# 85-2031.net
KiCad netlist of a schematic drawn in EAGLE
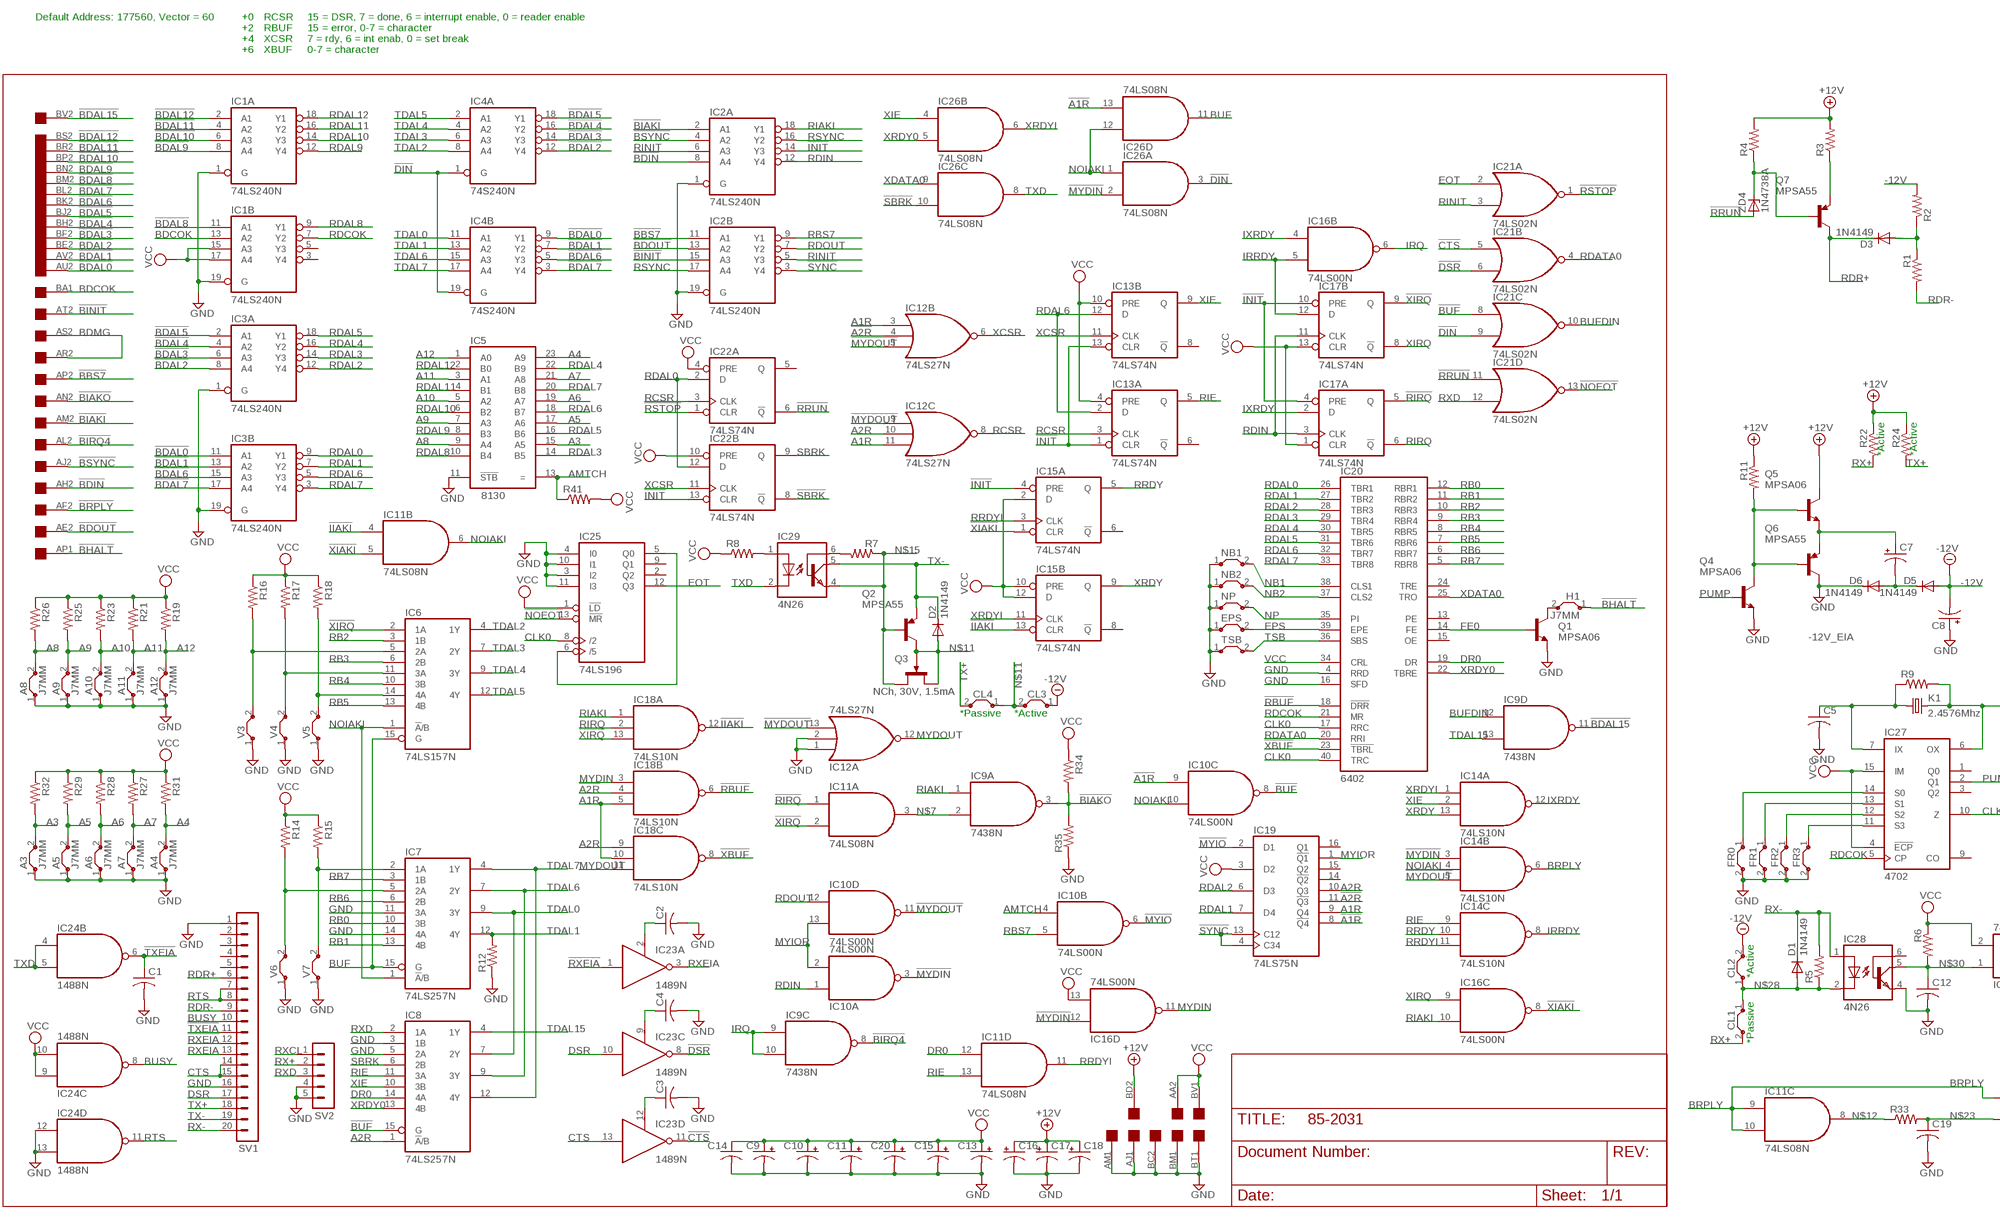
[diagram p0: schematic, sheet 1, part 1 of 2]
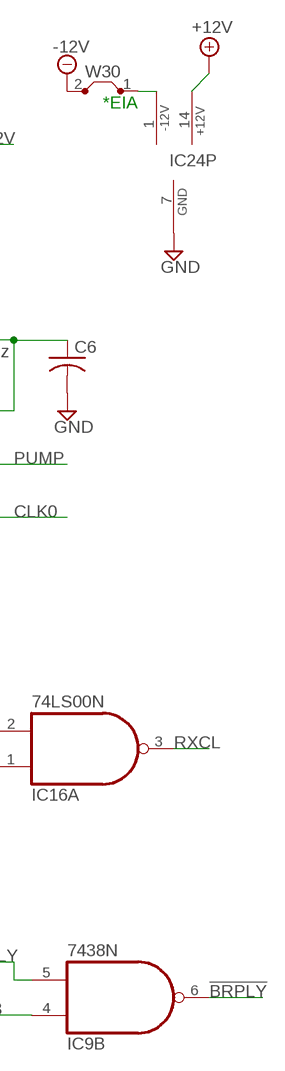
[diagram p1: schematic, sheet 1, part 2 of 2]

(export (version "E")
  (design (tool "Eeschema 10.0.6"))
  (components
    (comp (ref "A3")
      (value "J7MM")
      (footprint "eagle-import:07")
      (libsource (lib "eagle-import") (part "J7MM"))
    )
    (comp (ref "A4")
      (value "J7MM")
      (footprint "eagle-import:07")
      (libsource (lib "eagle-import") (part "J7MM"))
    )
    (comp (ref "A5")
      (value "J7MM")
      (footprint "eagle-import:07")
      (libsource (lib "eagle-import") (part "J7MM"))
    )
    (comp (ref "A6")
      (value "J7MM")
      (footprint "eagle-import:07")
      (libsource (lib "eagle-import") (part "J7MM"))
    )
    (comp (ref "A7")
      (value "J7MM")
      (footprint "eagle-import:07")
      (libsource (lib "eagle-import") (part "J7MM"))
    )
    (comp (ref "A8")
      (value "J7MM")
      (footprint "eagle-import:07")
      (libsource (lib "eagle-import") (part "J7MM"))
    )
    (comp (ref "A9")
      (value "J7MM")
      (footprint "eagle-import:07")
      (libsource (lib "eagle-import") (part "J7MM"))
    )
    (comp (ref "A10")
      (value "J7MM")
      (footprint "eagle-import:07")
      (libsource (lib "eagle-import") (part "J7MM"))
    )
    (comp (ref "A11")
      (value "J7MM")
      (footprint "eagle-import:07")
      (libsource (lib "eagle-import") (part "J7MM"))
    )
    (comp (ref "A12")
      (value "J7MM")
      (footprint "eagle-import:07")
      (libsource (lib "eagle-import") (part "J7MM"))
    )
    (comp (ref "C1")
      (value "C-US075-032X103")
      (footprint "eagle-import:C075-032X103")
      (libsource (lib "eagle-import") (part "C-US075-032X103"))
    )
    (comp (ref "C2")
      (value "C-US075-032X103")
      (footprint "eagle-import:C075-032X103")
      (libsource (lib "eagle-import") (part "C-US075-032X103"))
    )
    (comp (ref "C3")
      (value "C-US075-032X103")
      (footprint "eagle-import:C075-032X103")
      (libsource (lib "eagle-import") (part "C-US075-032X103"))
    )
    (comp (ref "C4")
      (value "C-US075-032X103")
      (footprint "eagle-import:C075-032X103")
      (libsource (lib "eagle-import") (part "C-US075-032X103"))
    )
    (comp (ref "C5")
      (value "C-US075-032X103")
      (footprint "eagle-import:C075-032X103")
      (libsource (lib "eagle-import") (part "C-US075-032X103"))
    )
    (comp (ref "C6")
      (value "C-US075-032X103")
      (footprint "eagle-import:C075-032X103")
      (libsource (lib "eagle-import") (part "C-US075-032X103"))
    )
    (comp (ref "C7")
      (value "CPOL-USB45181B")
      (footprint "eagle-import:B45181B")
      (libsource (lib "eagle-import") (part "CPOL-USB45181B"))
    )
    (comp (ref "C8")
      (value "CPOL-USB45181B")
      (footprint "eagle-import:B45181B")
      (libsource (lib "eagle-import") (part "CPOL-USB45181B"))
    )
    (comp (ref "C9")
      (value "CPOL-USB45181B")
      (footprint "eagle-import:B45181B")
      (libsource (lib "eagle-import") (part "CPOL-USB45181B"))
    )
    (comp (ref "C10")
      (value "CPOL-USB45181B")
      (footprint "eagle-import:B45181B")
      (libsource (lib "eagle-import") (part "CPOL-USB45181B"))
    )
    (comp (ref "C11")
      (value "CPOL-USB45181B")
      (footprint "eagle-import:B45181B")
      (libsource (lib "eagle-import") (part "CPOL-USB45181B"))
    )
    (comp (ref "C12")
      (value "C-US075-032X103")
      (footprint "eagle-import:C075-032X103")
      (libsource (lib "eagle-import") (part "C-US075-032X103"))
    )
    (comp (ref "C13")
      (value "CPOL-USB45181B")
      (footprint "eagle-import:B45181B")
      (libsource (lib "eagle-import") (part "CPOL-USB45181B"))
    )
    (comp (ref "C14")
      (value "C-US075-032X103")
      (footprint "eagle-import:C075-032X103")
      (libsource (lib "eagle-import") (part "C-US075-032X103"))
    )
    (comp (ref "C15")
      (value "CPOL-USB45181B")
      (footprint "eagle-import:B45181B")
      (libsource (lib "eagle-import") (part "CPOL-USB45181B"))
    )
    (comp (ref "C16")
      (value "CPOL-USB45181B")
      (footprint "eagle-import:B45181B")
      (libsource (lib "eagle-import") (part "CPOL-USB45181B"))
    )
    (comp (ref "C17")
      (value "CPOL-USB45181B")
      (footprint "eagle-import:B45181B")
      (libsource (lib "eagle-import") (part "CPOL-USB45181B"))
    )
    (comp (ref "C18")
      (value "CPOL-USB45181B")
      (footprint "eagle-import:B45181B")
      (libsource (lib "eagle-import") (part "CPOL-USB45181B"))
    )
    (comp (ref "C19")
      (value "C-US075-032X103")
      (footprint "eagle-import:C075-032X103")
      (libsource (lib "eagle-import") (part "C-US075-032X103"))
    )
    (comp (ref "C20")
      (value "CPOL-USB45181B")
      (footprint "eagle-import:B45181B")
      (libsource (lib "eagle-import") (part "CPOL-USB45181B"))
    )
    (comp (ref "CL1")
      (value "J7MM")
      (footprint "eagle-import:07")
      (libsource (lib "eagle-import") (part "J7MM"))
    )
    (comp (ref "CL2")
      (value "J7MM")
      (footprint "eagle-import:07")
      (libsource (lib "eagle-import") (part "J7MM"))
    )
    (comp (ref "CL3")
      (value "J7MM")
      (footprint "eagle-import:07")
      (libsource (lib "eagle-import") (part "J7MM"))
    )
    (comp (ref "CL4")
      (value "J7MM")
      (footprint "eagle-import:07")
      (libsource (lib "eagle-import") (part "J7MM"))
    )
    (comp (ref "D1")
      (value "1N4149")
      (footprint "eagle-import:DO35-10")
      (libsource (lib "eagle-import") (part "1N4148DO35-10"))
    )
    (comp (ref "D2")
      (value "1N4149")
      (footprint "eagle-import:DO35-10")
      (libsource (lib "eagle-import") (part "1N4148DO35-10"))
    )
    (comp (ref "D3")
      (value "1N4149")
      (footprint "eagle-import:DO35-10")
      (libsource (lib "eagle-import") (part "1N4148DO35-10"))
    )
    (comp (ref "D5")
      (value "1N4149")
      (footprint "eagle-import:DO35-10")
      (libsource (lib "eagle-import") (part "1N4148DO35-10"))
    )
    (comp (ref "D6")
      (value "1N4149")
      (footprint "eagle-import:DO35-10")
      (libsource (lib "eagle-import") (part "1N4148DO35-10"))
    )
    (comp (ref "EDGE$")
      (value "DOUBLE")
      (footprint "eagle-import:EDGE-CON4")
      (libsource (lib "eagle-import") (part "DOUBLE"))
    )
    (comp (ref "EPS")
      (value "J7MM")
      (footprint "eagle-import:07")
      (libsource (lib "eagle-import") (part "J7MM"))
    )
    (comp (ref "FR0")
      (value "J7MM")
      (footprint "eagle-import:07")
      (libsource (lib "eagle-import") (part "J7MM"))
    )
    (comp (ref "FR1")
      (value "J7MM")
      (footprint "eagle-import:07")
      (libsource (lib "eagle-import") (part "J7MM"))
    )
    (comp (ref "FR2")
      (value "J7MM")
      (footprint "eagle-import:07")
      (libsource (lib "eagle-import") (part "J7MM"))
    )
    (comp (ref "FR3")
      (value "J7MM")
      (footprint "eagle-import:07")
      (libsource (lib "eagle-import") (part "J7MM"))
    )
    (comp (ref "H1")
      (value "J7MM")
      (footprint "eagle-import:07")
      (libsource (lib "eagle-import") (part "J7MM"))
    )
    (comp (ref "IC1")
      (value "74LS240N")
      (footprint "eagle-import:DIL20")
      (libsource (lib "eagle-import") (part "74240NLS"))
    )
    (comp (ref "IC2")
      (value "74LS240N")
      (footprint "eagle-import:DIL20")
      (libsource (lib "eagle-import") (part "74240NLS"))
    )
    (comp (ref "IC3")
      (value "74LS240N")
      (footprint "eagle-import:DIL20")
      (libsource (lib "eagle-import") (part "74240NLS"))
    )
    (comp (ref "IC4")
      (value "74S240N")
      (footprint "eagle-import:DIL20")
      (libsource (lib "eagle-import") (part "74240NS"))
    )
    (comp (ref "IC5")
      (value "8130")
      (footprint "eagle-import:DIL24")
      (libsource (lib "eagle-import") (part "8130"))
    )
    (comp (ref "IC6")
      (value "74LS157N")
      (footprint "eagle-import:DIL16")
      (libsource (lib "eagle-import") (part "74157NLS"))
    )
    (comp (ref "IC7")
      (value "74LS257N")
      (footprint "eagle-import:DIL16")
      (libsource (lib "eagle-import") (part "74257NLS"))
    )
    (comp (ref "IC8")
      (value "74LS257N")
      (footprint "eagle-import:DIL16")
      (libsource (lib "eagle-import") (part "74257NLS"))
    )
    (comp (ref "IC9")
      (value "7438N")
      (footprint "eagle-import:DIL14")
      (libsource (lib "eagle-import") (part "7438NLS"))
    )
    (comp (ref "IC10")
      (value "74LS00N")
      (footprint "eagle-import:DIL14")
      (libsource (lib "eagle-import") (part "7400NLS"))
    )
    (comp (ref "IC11")
      (value "74LS08N")
      (footprint "eagle-import:DIL14")
      (libsource (lib "eagle-import") (part "7408NLS"))
    )
    (comp (ref "IC12")
      (value "74LS27N")
      (footprint "eagle-import:DIL14")
      (libsource (lib "eagle-import") (part "7427NLS"))
    )
    (comp (ref "IC13")
      (value "74LS74N")
      (footprint "eagle-import:DIL14")
      (libsource (lib "eagle-import") (part "7474NLS"))
    )
    (comp (ref "IC14")
      (value "74LS10N")
      (footprint "eagle-import:DIL14")
      (libsource (lib "eagle-import") (part "7410NLS"))
    )
    (comp (ref "IC15")
      (value "74LS74N")
      (footprint "eagle-import:DIL14")
      (libsource (lib "eagle-import") (part "7474NLS"))
    )
    (comp (ref "IC16")
      (value "74LS00N")
      (footprint "eagle-import:DIL14")
      (libsource (lib "eagle-import") (part "7400NLS"))
    )
    (comp (ref "IC17")
      (value "74LS74N")
      (footprint "eagle-import:DIL14")
      (libsource (lib "eagle-import") (part "7474NLS"))
    )
    (comp (ref "IC18")
      (value "74LS10N")
      (footprint "eagle-import:DIL14")
      (libsource (lib "eagle-import") (part "7410NLS"))
    )
    (comp (ref "IC19")
      (value "74LS75N")
      (footprint "eagle-import:DIL16")
      (libsource (lib "eagle-import") (part "7475NLS"))
    )
    (comp (ref "IC20")
      (value "6402")
      (footprint "eagle-import:DIL40")
      (libsource (lib "eagle-import") (part "HD6402"))
    )
    (comp (ref "IC21")
      (value "74LS02N")
      (footprint "eagle-import:DIL14")
      (libsource (lib "eagle-import") (part "7402NLS"))
    )
    (comp (ref "IC22")
      (value "74LS74N")
      (footprint "eagle-import:DIL14")
      (libsource (lib "eagle-import") (part "7474NLS"))
    )
    (comp (ref "IC23")
      (value "1489N")
      (footprint "eagle-import:DIL14")
      (libsource (lib "eagle-import") (part "1489N"))
    )
    (comp (ref "IC24")
      (value "1488N")
      (footprint "eagle-import:DIL14")
      (libsource (lib "eagle-import") (part "1488N"))
    )
    (comp (ref "IC25")
      (value "74LS196")
      (footprint "eagle-import:DIL14")
      (libsource (lib "eagle-import") (part "74LS196"))
    )
    (comp (ref "IC26")
      (value "74LS08N")
      (footprint "eagle-import:DIL14")
      (libsource (lib "eagle-import") (part "7408NLS"))
    )
    (comp (ref "IC27")
      (value "4702")
      (footprint "eagle-import:DIL16")
      (libsource (lib "eagle-import") (part "HD4702"))
    )
    (comp (ref "IC28")
      (value "4N26")
      (footprint "eagle-import:DIL06")
      (fields (field (name "MF") "FAIRCHILD SEMICONDUCTOR") (field (name "MPN") "4N35"))
      (libsource (lib "eagle-import") (part "4N35"))
    )
    (comp (ref "IC29")
      (value "4N26")
      (footprint "eagle-import:DIL06")
      (fields (field (name "MF") "FAIRCHILD SEMICONDUCTOR") (field (name "MPN") "4N35"))
      (libsource (lib "eagle-import") (part "4N35"))
    )
    (comp (ref "K1")
      (value "2.4576Mhz")
      (footprint "eagle-import:HC33U-H")
      (libsource (lib "eagle-import") (part "CRYSTALHC33U-H"))
    )
    (comp (ref "NB1")
      (value "J7MM")
      (footprint "eagle-import:07")
      (libsource (lib "eagle-import") (part "J7MM"))
    )
    (comp (ref "NB2")
      (value "J7MM")
      (footprint "eagle-import:07")
      (libsource (lib "eagle-import") (part "J7MM"))
    )
    (comp (ref "NP")
      (value "J7MM")
      (footprint "eagle-import:07")
      (libsource (lib "eagle-import") (part "J7MM"))
    )
    (comp (ref "Q1")
      (value "MPSA06")
      (footprint "eagle-import:TO92L")
      (libsource (lib "eagle-import") (part "-NPN-TO92L"))
    )
    (comp (ref "Q2")
      (value "MPSA55")
      (footprint "eagle-import:TO92L")
      (libsource (lib "eagle-import") (part "-PNP-TO92L"))
    )
    (comp (ref "Q3")
      (value "NCh, 30V, 1.5mA")
      (footprint "eagle-import:TO18E")
      (libsource (lib "eagle-import") (part "2N4391"))
    )
    (comp (ref "Q4")
      (value "MPSA06")
      (footprint "eagle-import:TO92L")
      (libsource (lib "eagle-import") (part "-NPN-TO92L"))
    )
    (comp (ref "Q5")
      (value "MPSA06")
      (footprint "eagle-import:TO92L")
      (libsource (lib "eagle-import") (part "-NPN-TO92L"))
    )
    (comp (ref "Q6")
      (value "MPSA55")
      (footprint "eagle-import:TO92L")
      (libsource (lib "eagle-import") (part "-PNP-TO92L"))
    )
    (comp (ref "Q7")
      (value "MPSA55")
      (footprint "eagle-import:TO92L")
      (libsource (lib "eagle-import") (part "-PNP-TO92L"))
    )
    (comp (ref "R1")
      (value "R-US_0207/10")
      (footprint "eagle-import:0207_10")
      (libsource (lib "eagle-import") (part "R-US_0207/10"))
    )
    (comp (ref "R2")
      (value "R-US_0207/10")
      (footprint "eagle-import:0207_10")
      (libsource (lib "eagle-import") (part "R-US_0207/10"))
    )
    (comp (ref "R3")
      (value "R-US_0207/10")
      (footprint "eagle-import:0207_10")
      (libsource (lib "eagle-import") (part "R-US_0207/10"))
    )
    (comp (ref "R4")
      (value "R-US_0207/10")
      (footprint "eagle-import:0207_10")
      (libsource (lib "eagle-import") (part "R-US_0207/10"))
    )
    (comp (ref "R5")
      (value "R-US_0207/10")
      (footprint "eagle-import:0207_10")
      (libsource (lib "eagle-import") (part "R-US_0207/10"))
    )
    (comp (ref "R6")
      (value "R-US_0207/10")
      (footprint "eagle-import:0207_10")
      (libsource (lib "eagle-import") (part "R-US_0207/10"))
    )
    (comp (ref "R7")
      (value "R-US_0207/10")
      (footprint "eagle-import:0207_10")
      (libsource (lib "eagle-import") (part "R-US_0207/10"))
    )
    (comp (ref "R8")
      (value "R-US_0207/10")
      (footprint "eagle-import:0207_10")
      (libsource (lib "eagle-import") (part "R-US_0207/10"))
    )
    (comp (ref "R9")
      (value "R-US_0207/10")
      (footprint "eagle-import:0207_10")
      (libsource (lib "eagle-import") (part "R-US_0207/10"))
    )
    (comp (ref "R11")
      (value "R-US_0411/12")
      (footprint "eagle-import:0411_12")
      (libsource (lib "eagle-import") (part "R-US_0411/12"))
    )
    (comp (ref "R12")
      (value "R-US_0207/10")
      (footprint "eagle-import:0207_10")
      (libsource (lib "eagle-import") (part "R-US_0207/10"))
    )
    (comp (ref "R14")
      (value "R-US_0207/10")
      (footprint "eagle-import:0207_10")
      (libsource (lib "eagle-import") (part "R-US_0207/10"))
    )
    (comp (ref "R15")
      (value "R-US_0207/10")
      (footprint "eagle-import:0207_10")
      (libsource (lib "eagle-import") (part "R-US_0207/10"))
    )
    (comp (ref "R16")
      (value "R-US_0207/10")
      (footprint "eagle-import:0207_10")
      (libsource (lib "eagle-import") (part "R-US_0207/10"))
    )
    (comp (ref "R17")
      (value "R-US_0207/10")
      (footprint "eagle-import:0207_10")
      (libsource (lib "eagle-import") (part "R-US_0207/10"))
    )
    (comp (ref "R18")
      (value "R-US_0207/10")
      (footprint "eagle-import:0207_10")
      (libsource (lib "eagle-import") (part "R-US_0207/10"))
    )
    (comp (ref "R19")
      (value "R-US_0207/10")
      (footprint "eagle-import:0207_10")
      (libsource (lib "eagle-import") (part "R-US_0207/10"))
    )
    (comp (ref "R21")
      (value "R-US_0207/10")
      (footprint "eagle-import:0207_10")
      (libsource (lib "eagle-import") (part "R-US_0207/10"))
    )
    (comp (ref "R22")
      (value "R-US_0207/10")
      (footprint "eagle-import:0207_10")
      (libsource (lib "eagle-import") (part "R-US_0207/10"))
    )
    (comp (ref "R23")
      (value "R-US_0207/10")
      (footprint "eagle-import:0207_10")
      (libsource (lib "eagle-import") (part "R-US_0207/10"))
    )
    (comp (ref "R24")
      (value "R-US_0207/10")
      (footprint "eagle-import:0207_10")
      (libsource (lib "eagle-import") (part "R-US_0207/10"))
    )
    (comp (ref "R25")
      (value "R-US_0207/10")
      (footprint "eagle-import:0207_10")
      (libsource (lib "eagle-import") (part "R-US_0207/10"))
    )
    (comp (ref "R26")
      (value "R-US_0207/10")
      (footprint "eagle-import:0207_10")
      (libsource (lib "eagle-import") (part "R-US_0207/10"))
    )
    (comp (ref "R27")
      (value "R-US_0207/10")
      (footprint "eagle-import:0207_10")
      (libsource (lib "eagle-import") (part "R-US_0207/10"))
    )
    (comp (ref "R28")
      (value "R-US_0207/10")
      (footprint "eagle-import:0207_10")
      (libsource (lib "eagle-import") (part "R-US_0207/10"))
    )
    (comp (ref "R29")
      (value "R-US_0207/10")
      (footprint "eagle-import:0207_10")
      (libsource (lib "eagle-import") (part "R-US_0207/10"))
    )
    (comp (ref "R31")
      (value "R-US_0207/10")
      (footprint "eagle-import:0207_10")
      (libsource (lib "eagle-import") (part "R-US_0207/10"))
    )
    (comp (ref "R32")
      (value "R-US_0207/10")
      (footprint "eagle-import:0207_10")
      (libsource (lib "eagle-import") (part "R-US_0207/10"))
    )
    (comp (ref "R33")
      (value "R-US_0207/10")
      (footprint "eagle-import:0207_10")
      (libsource (lib "eagle-import") (part "R-US_0207/10"))
    )
    (comp (ref "R34")
      (value "R-US_0207/10")
      (footprint "eagle-import:0207_10")
      (libsource (lib "eagle-import") (part "R-US_0207/10"))
    )
    (comp (ref "R35")
      (value "R-US_0207/10")
      (footprint "eagle-import:0207_10")
      (libsource (lib "eagle-import") (part "R-US_0207/10"))
    )
    (comp (ref "R41")
      (value "R-US_0207/10")
      (footprint "eagle-import:0207_10")
      (libsource (lib "eagle-import") (part "R-US_0207/10"))
    )
    (comp (ref "SV1")
      (value "MA20-1")
      (footprint "eagle-import:MA20-1")
      (libsource (lib "eagle-import") (part "MA20-1"))
    )
    (comp (ref "SV2")
      (value "MA05-1")
      (footprint "eagle-import:MA05-1")
      (libsource (lib "eagle-import") (part "MA05-1"))
    )
    (comp (ref "TSB")
      (value "J7MM")
      (footprint "eagle-import:07")
      (libsource (lib "eagle-import") (part "J7MM"))
    )
    (comp (ref "V3")
      (value "J7MM")
      (footprint "eagle-import:07")
      (libsource (lib "eagle-import") (part "J7MM"))
    )
    (comp (ref "V4")
      (value "J7MM")
      (footprint "eagle-import:07")
      (libsource (lib "eagle-import") (part "J7MM"))
    )
    (comp (ref "V5")
      (value "J7MM")
      (footprint "eagle-import:07")
      (libsource (lib "eagle-import") (part "J7MM"))
    )
    (comp (ref "V6")
      (value "J7MM")
      (footprint "eagle-import:07")
      (libsource (lib "eagle-import") (part "J7MM"))
    )
    (comp (ref "V7")
      (value "J7MM")
      (footprint "eagle-import:07")
      (libsource (lib "eagle-import") (part "J7MM"))
    )
    (comp (ref "W30")
      (value "J7MM")
      (footprint "eagle-import:07")
      (libsource (lib "eagle-import") (part "J7MM"))
    )
    (comp (ref "ZD4")
      (value "1N4738A")
      (footprint "eagle-import:DO41Z10")
      (libsource (lib "eagle-import") (part "1N4728"))
    )
  )
  (nets
    (net (code "1") (name "+12V") (class "Default")
      (node (ref "C16") (pin "+") (pinfunction "+_+") (pintype "passive"))
      (node (ref "C17") (pin "+") (pinfunction "+_+") (pintype "passive"))
      (node (ref "C18") (pin "+") (pinfunction "+_+") (pintype "passive"))
      (node (ref "EDGE$") (pin "BD2") (pinfunction "1_BD2") (pintype "bidirectional"))
      (node (ref "IC24") (pin "14") (pinfunction "+12V_14") (pintype "power_in"))
      (node (ref "Q5") (pin "3") (pinfunction "C_3") (pintype "passive"))
      (node (ref "R11") (pin "1") (pinfunction "1_1") (pintype "passive"))
      (node (ref "R22") (pin "1") (pinfunction "1_1") (pintype "passive"))
      (node (ref "R24") (pin "1") (pinfunction "1_1") (pintype "passive"))
      (node (ref "R3") (pin "2") (pinfunction "2_2") (pintype "passive"))
      (node (ref "R4") (pin "2") (pinfunction "2_2") (pintype "passive"))
    )
    (net (code "2") (name "-12V") (class "Default")
      (node (ref "C8") (pin "-") (pinfunction "-_-") (pintype "passive"))
      (node (ref "CL2") (pin "2") (pinfunction "2_2") (pintype "passive"))
      (node (ref "CL3") (pin "1") (pinfunction "1_1") (pintype "passive"))
      (node (ref "D5") (pin "A") (pinfunction "A_A") (pintype "passive"))
      (node (ref "R2") (pin "2") (pinfunction "2_2") (pintype "passive"))
      (node (ref "W30") (pin "2") (pinfunction "2_2") (pintype "passive"))
    )
    (net (code "3") (name "/-12V_EIA") (class "Default")
      (node (ref "IC24") (pin "1") (pinfunction "-12V_1") (pintype "power_in"))
      (node (ref "W30") (pin "1") (pinfunction "1_1") (pintype "passive"))
    )
    (net (code "4") (name "/A1R") (class "Default")
      (node (ref "IC12") (pin "11") (pinfunction "I2_11") (pintype "input"))
      (node (ref "IC12") (pin "3") (pinfunction "I0_3") (pintype "input"))
      (node (ref "IC18") (pin "10") (pinfunction "I1_10") (pintype "input"))
      (node (ref "IC18") (pin "5") (pinfunction "I2_5") (pintype "input"))
      (node (ref "IC19") (pin "9") (pinfunction "Q4_9") (pintype "output"))
    )
    (net (code "5") (name "/A2R") (class "Default")
      (node (ref "IC12") (pin "10") (pinfunction "I1_10") (pintype "input"))
      (node (ref "IC18") (pin "9") (pinfunction "I0_9") (pintype "input"))
      (node (ref "IC19") (pin "10") (pinfunction "Q3_10") (pintype "output"))
      (node (ref "IC8") (pin "1") (pinfunction "~{A}/B_1") (pintype "input"))
    )
    (net (code "6") (name "/A3") (class "Default")
      (node (ref "A3") (pin "2") (pinfunction "2_2") (pintype "passive"))
      (node (ref "IC5") (pin "15") (pinfunction "A5_15") (pintype "input"))
      (node (ref "R32") (pin "2") (pinfunction "2_2") (pintype "passive"))
    )
    (net (code "7") (name "/A4") (class "Default")
      (node (ref "A4") (pin "2") (pinfunction "2_2") (pintype "passive"))
      (node (ref "IC5") (pin "23") (pinfunction "A9_23") (pintype "input"))
      (node (ref "R31") (pin "2") (pinfunction "2_2") (pintype "passive"))
    )
    (net (code "8") (name "/A5") (class "Default")
      (node (ref "A5") (pin "2") (pinfunction "2_2") (pintype "passive"))
      (node (ref "IC5") (pin "17") (pinfunction "A6_17") (pintype "input"))
      (node (ref "R29") (pin "2") (pinfunction "2_2") (pintype "passive"))
    )
    (net (code "9") (name "/A6") (class "Default")
      (node (ref "A6") (pin "2") (pinfunction "2_2") (pintype "passive"))
      (node (ref "IC5") (pin "19") (pinfunction "A7_19") (pintype "input"))
      (node (ref "R28") (pin "2") (pinfunction "2_2") (pintype "passive"))
    )
    (net (code "10") (name "/A7") (class "Default")
      (node (ref "A7") (pin "2") (pinfunction "2_2") (pintype "passive"))
      (node (ref "IC5") (pin "21") (pinfunction "A8_21") (pintype "input"))
      (node (ref "R27") (pin "2") (pinfunction "2_2") (pintype "passive"))
    )
    (net (code "11") (name "/A8") (class "Default")
      (node (ref "A8") (pin "2") (pinfunction "2_2") (pintype "passive"))
      (node (ref "IC5") (pin "9") (pinfunction "A4_9") (pintype "input"))
      (node (ref "R26") (pin "2") (pinfunction "2_2") (pintype "passive"))
    )
    (net (code "12") (name "/A9") (class "Default")
      (node (ref "A9") (pin "2") (pinfunction "2_2") (pintype "passive"))
      (node (ref "IC5") (pin "7") (pinfunction "A3_7") (pintype "input"))
      (node (ref "R25") (pin "2") (pinfunction "2_2") (pintype "passive"))
    )
    (net (code "13") (name "/A10") (class "Default")
      (node (ref "A10") (pin "2") (pinfunction "2_2") (pintype "passive"))
      (node (ref "IC5") (pin "5") (pinfunction "A2_5") (pintype "input"))
      (node (ref "R23") (pin "2") (pinfunction "2_2") (pintype "passive"))
    )
    (net (code "14") (name "/A11") (class "Default")
      (node (ref "A11") (pin "2") (pinfunction "2_2") (pintype "passive"))
      (node (ref "IC5") (pin "3") (pinfunction "A1_3") (pintype "input"))
      (node (ref "R21") (pin "2") (pinfunction "2_2") (pintype "passive"))
    )
    (net (code "15") (name "/A12") (class "Default")
      (node (ref "A12") (pin "2") (pinfunction "2_2") (pintype "passive"))
      (node (ref "IC5") (pin "1") (pinfunction "A0_1") (pintype "input"))
      (node (ref "R19") (pin "2") (pinfunction "2_2") (pintype "passive"))
    )
    (net (code "16") (name "/AMTCH") (class "Default")
      (node (ref "IC10") (pin "4") (pinfunction "I0_4") (pintype "input"))
      (node (ref "IC5") (pin "13") (pinfunction "=_13") (pintype "output"))
      (node (ref "R41") (pin "1") (pinfunction "1_1") (pintype "passive"))
    )
    (net (code "17") (name "/BDCOK") (class "Default")
      (node (ref "EDGE$") (pin "BA1") (pinfunction "1_BA1") (pintype "bidirectional"))
      (node (ref "IC1") (pin "13") (pinfunction "A2_13") (pintype "input"))
    )
    (net (code "18") (name "/BDMG") (class "Default")
      (node (ref "EDGE$") (pin "AR2") (pinfunction "1_AR2") (pintype "bidirectional"))
      (node (ref "EDGE$") (pin "AS2") (pinfunction "1_AS2") (pintype "bidirectional"))
    )
    (net (code "19") (name "/BRPLY") (class "Default")
      (node (ref "IC11") (pin "10") (pinfunction "I1_10") (pintype "input"))
      (node (ref "IC11") (pin "9") (pinfunction "I0_9") (pintype "input"))
      (node (ref "IC14") (pin "6") (pinfunction "O_6") (pintype "output"))
      (node (ref "IC9") (pin "5") (pinfunction "I1_5") (pintype "input"))
    )
    (net (code "20") (name "/BUF") (class "Default")
      (node (ref "IC26") (pin "11") (pinfunction "O_11") (pintype "output"))
      (node (ref "IC6") (pin "15") (pinfunction "G_15") (pintype "input"))
      (node (ref "IC7") (pin "15") (pinfunction "G_15") (pintype "input"))
    )
    (net (code "21") (name "/BUFDIN") (class "Default")
      (node (ref "IC21") (pin "10") (pinfunction "O_10") (pintype "output"))
      (node (ref "IC9") (pin "12") (pinfunction "I0_12") (pintype "input"))
    )
    (net (code "22") (name "/BUSY") (class "Default")
      (node (ref "IC24") (pin "8") (pinfunction "O_8") (pintype "output"))
      (node (ref "SV1") (pin "10") (pinfunction "10_10") (pintype "passive"))
    )
    (net (code "23") (name "/CLK0") (class "Default")
      (node (ref "IC20") (pin "17") (pinfunction "RRC_17") (pintype "input"))
      (node (ref "IC20") (pin "40") (pinfunction "TRC_40") (pintype "input"))
      (node (ref "IC25") (pin "8") (pinfunction "/2_8") (pintype "bidirectional"))
      (node (ref "IC27") (pin "10") (pinfunction "Z_10") (pintype "output"))
    )
    (net (code "24") (name "/CTS") (class "Default")
      (node (ref "IC23") (pin "13") (pinfunction "I_13") (pintype "input"))
      (node (ref "SV1") (pin "14") (pinfunction "14_14") (pintype "passive"))
      (node (ref "SV1") (pin "15") (pinfunction "15_15") (pintype "passive"))
    )
    (net (code "25") (name "/DR0") (class "Default")
      (node (ref "IC11") (pin "12") (pinfunction "I0_12") (pintype "input"))
      (node (ref "IC20") (pin "19") (pinfunction "DR_19") (pintype "tri_state"))
      (node (ref "IC8") (pin "14") (pinfunction "4A_14") (pintype "input"))
    )
    (net (code "26") (name "/DSR") (class "Default")
      (node (ref "IC23") (pin "10") (pinfunction "I_10") (pintype "input"))
      (node (ref "SV1") (pin "17") (pinfunction "17_17") (pintype "passive"))
    )
    (net (code "27") (name "/EOT") (class "Default")
      (node (ref "IC21") (pin "2") (pinfunction "I0_2") (pintype "input"))
      (node (ref "IC25") (pin "12") (pinfunction "Q3_12") (pintype "output"))
    )
    (net (code "28") (name "/EPS") (class "Default")
      (node (ref "EPS") (pin "2") (pinfunction "2_2") (pintype "passive"))
      (node (ref "IC20") (pin "39") (pinfunction "EPE_39") (pintype "input"))
    )
    (net (code "29") (name "/FE0") (class "Default")
      (node (ref "IC20") (pin "14") (pinfunction "FE_14") (pintype "tri_state"))
      (node (ref "Q1") (pin "2") (pinfunction "B_2") (pintype "passive"))
    )
    (net (code "30") (name "/IRQ") (class "Default")
      (node (ref "IC16") (pin "6") (pinfunction "O_6") (pintype "output"))
      (node (ref "IC9") (pin "10") (pinfunction "I1_10") (pintype "input"))
      (node (ref "IC9") (pin "9") (pinfunction "I0_9") (pintype "input"))
    )
    (net (code "31") (name "/IRRDY") (class "Default")
      (node (ref "IC14") (pin "8") (pinfunction "O_8") (pintype "output"))
      (node (ref "IC16") (pin "5") (pinfunction "I1_5") (pintype "input"))
      (node (ref "IC17") (pin "12") (pinfunction "D_12") (pintype "input"))
    )
    (net (code "32") (name "/IXRDY") (class "Default")
      (node (ref "IC14") (pin "12") (pinfunction "O_12") (pintype "output"))
      (node (ref "IC16") (pin "4") (pinfunction "I0_4") (pintype "input"))
      (node (ref "IC17") (pin "2") (pinfunction "D_2") (pintype "input"))
    )
    (net (code "33") (name "/MYDIN") (class "Default")
      (node (ref "IC16") (pin "11") (pinfunction "O_11") (pintype "output"))
      (node (ref "IC18") (pin "3") (pinfunction "I0_3") (pintype "input"))
    )
    (net (code "34") (name "/MYDOUT") (class "Default")
      (node (ref "IC12") (pin "12") (pinfunction "O_12") (pintype "output"))
      (node (ref "IC18") (pin "11") (pinfunction "I2_11") (pintype "input"))
    )
    (net (code "35") (name "/MYIOR") (class "Default")
      (node (ref "IC10") (pin "13") (pinfunction "I1_13") (pintype "input"))
      (node (ref "IC10") (pin "2") (pinfunction "I1_2") (pintype "input"))
      (node (ref "IC19") (pin "1") (pinfunction "~{Q1}_1") (pintype "output"))
    )
    (net (code "36") (name "/N$7") (class "Default")
      (node (ref "IC11") (pin "3") (pinfunction "O_3") (pintype "output"))
      (node (ref "IC9") (pin "2") (pinfunction "I1_2") (pintype "input"))
    )
    (net (code "37") (name "/N$11") (class "Default")
      (node (ref "CL3") (pin "2") (pinfunction "2_2") (pintype "passive"))
      (node (ref "CL4") (pin "1") (pinfunction "1_1") (pintype "passive"))
      (node (ref "D2") (pin "A") (pinfunction "A_A") (pintype "passive"))
      (node (ref "Q2") (pin "3") (pinfunction "C_3") (pintype "passive"))
      (node (ref "Q3") (pin "D") (pinfunction "D_D") (pintype "passive"))
      (node (ref "Q3") (pin "G") (pinfunction "G_G") (pintype "passive"))
    )
    (net (code "38") (name "/N$12") (class "Default")
      (node (ref "IC11") (pin "8") (pinfunction "O_8") (pintype "output"))
      (node (ref "R33") (pin "1") (pinfunction "1_1") (pintype "passive"))
    )
    (net (code "39") (name "/N$15") (class "Default")
      (node (ref "IC29") (pin "4") (pinfunction "EMI_4") (pintype "passive"))
      (node (ref "Q2") (pin "2") (pinfunction "B_2") (pintype "passive"))
      (node (ref "Q3") (pin "S") (pinfunction "S_S") (pintype "passive"))
      (node (ref "R7") (pin "1") (pinfunction "1_1") (pintype "passive"))
    )
    (net (code "40") (name "/N$23") (class "Default")
      (node (ref "C19") (pin "1") (pinfunction "1_1") (pintype "passive"))
      (node (ref "IC9") (pin "4") (pinfunction "I0_4") (pintype "input"))
      (node (ref "R33") (pin "2") (pinfunction "2_2") (pintype "passive"))
    )
    (net (code "41") (name "/N$28") (class "Default")
      (node (ref "CL1") (pin "1") (pinfunction "1_1") (pintype "passive"))
      (node (ref "CL2") (pin "1") (pinfunction "1_1") (pintype "passive"))
      (node (ref "D1") (pin "A") (pinfunction "A_A") (pintype "passive"))
      (node (ref "IC28") (pin "2") (pinfunction "C_2") (pintype "passive"))
      (node (ref "R5") (pin "1") (pinfunction "1_1") (pintype "passive"))
    )
    (net (code "42") (name "/N$30") (class "Default")
      (node (ref "C12") (pin "1") (pinfunction "1_1") (pintype "passive"))
      (node (ref "IC16") (pin "1") (pinfunction "I0_1") (pintype "input"))
      (node (ref "IC28") (pin "5") (pinfunction "COL_5") (pintype "passive"))
      (node (ref "R6") (pin "2") (pinfunction "2_2") (pintype "passive"))
    )
    (net (code "43") (name "/NB1") (class "Default")
      (node (ref "IC20") (pin "38") (pinfunction "CLS1_38") (pintype "input"))
      (node (ref "NB1") (pin "2") (pinfunction "2_2") (pintype "passive"))
    )
    (net (code "44") (name "/NB2") (class "Default")
      (node (ref "IC20") (pin "37") (pinfunction "CLS2_37") (pintype "input"))
      (node (ref "NB2") (pin "2") (pinfunction "2_2") (pintype "passive"))
    )
    (net (code "45") (name "/NOIAKI") (class "Default")
      (node (ref "IC10") (pin "10") (pinfunction "I1_10") (pintype "input"))
      (node (ref "IC11") (pin "6") (pinfunction "O_6") (pintype "output"))
      (node (ref "IC14") (pin "4") (pinfunction "I1_4") (pintype "input"))
      (node (ref "IC26") (pin "1") (pinfunction "I0_1") (pintype "input"))
      (node (ref "IC26") (pin "12") (pinfunction "I0_12") (pintype "input"))
      (node (ref "IC6") (pin "1") (pinfunction "~{A}/B_1") (pintype "input"))
      (node (ref "IC7") (pin "1") (pinfunction "~{A}/B_1") (pintype "input"))
    )
    (net (code "46") (name "/NP") (class "Default")
      (node (ref "IC20") (pin "35") (pinfunction "PI_35") (pintype "input"))
      (node (ref "NP") (pin "2") (pinfunction "2_2") (pintype "passive"))
    )
    (net (code "47") (name "/PUMP") (class "Default")
      (node (ref "IC27") (pin "2") (pinfunction "Q1_2") (pintype "output"))
      (node (ref "Q4") (pin "2") (pinfunction "B_2") (pintype "passive"))
    )
    (net (code "48") (name "/RB0") (class "Default")
      (node (ref "IC20") (pin "12") (pinfunction "RBR1_12") (pintype "tri_state"))
      (node (ref "IC7") (pin "10") (pinfunction "3B_10") (pintype "input"))
    )
    (net (code "49") (name "/RB1") (class "Default")
      (node (ref "IC20") (pin "11") (pinfunction "RBR2_11") (pintype "tri_state"))
      (node (ref "IC7") (pin "13") (pinfunction "4B_13") (pintype "input"))
    )
    (net (code "50") (name "/RB2") (class "Default")
      (node (ref "IC20") (pin "10") (pinfunction "RBR3_10") (pintype "tri_state"))
      (node (ref "IC6") (pin "3") (pinfunction "1B_3") (pintype "input"))
    )
    (net (code "51") (name "/RB3") (class "Default")
      (node (ref "IC20") (pin "9") (pinfunction "RBR4_9") (pintype "tri_state"))
      (node (ref "IC6") (pin "6") (pinfunction "2B_6") (pintype "input"))
    )
    (net (code "52") (name "/RB4") (class "Default")
      (node (ref "IC20") (pin "8") (pinfunction "RBR5_8") (pintype "tri_state"))
      (node (ref "IC6") (pin "10") (pinfunction "3B_10") (pintype "input"))
    )
    (net (code "53") (name "/RB5") (class "Default")
      (node (ref "IC20") (pin "7") (pinfunction "RBR6_7") (pintype "tri_state"))
      (node (ref "IC6") (pin "13") (pinfunction "4B_13") (pintype "input"))
    )
    (net (code "54") (name "/RB6") (class "Default")
      (node (ref "IC20") (pin "6") (pinfunction "RBR7_6") (pintype "tri_state"))
      (node (ref "IC7") (pin "6") (pinfunction "2B_6") (pintype "input"))
    )
    (net (code "55") (name "/RB7") (class "Default")
      (node (ref "IC20") (pin "5") (pinfunction "RBR8_5") (pintype "tri_state"))
      (node (ref "IC7") (pin "3") (pinfunction "1B_3") (pintype "input"))
    )
    (net (code "56") (name "/RBS7") (class "Default")
      (node (ref "IC10") (pin "5") (pinfunction "I1_5") (pintype "input"))
      (node (ref "IC2") (pin "9") (pinfunction "Y1_9") (pintype "tri_state"))
    )
    (net (code "57") (name "/RCSR") (class "Default")
      (node (ref "IC12") (pin "8") (pinfunction "O_8") (pintype "output"))
      (node (ref "IC13") (pin "3") (pinfunction "CLK_3") (pintype "input"))
      (node (ref "IC22") (pin "3") (pinfunction "CLK_3") (pintype "input"))
    )
    (net (code "58") (name "/RDAL0") (class "Default")
      (node (ref "IC20") (pin "26") (pinfunction "TBR1_26") (pintype "input"))
      (node (ref "IC22") (pin "12") (pinfunction "D_12") (pintype "input"))
      (node (ref "IC22") (pin "2") (pinfunction "D_2") (pintype "input"))
      (node (ref "IC3") (pin "9") (pinfunction "Y1_9") (pintype "tri_state"))
    )
    (net (code "59") (name "/RDAL1") (class "Default")
      (node (ref "IC19") (pin "7") (pinfunction "D4_7") (pintype "input"))
      (node (ref "IC20") (pin "27") (pinfunction "TBR2_27") (pintype "input"))
      (node (ref "IC3") (pin "7") (pinfunction "Y2_7") (pintype "tri_state"))
    )
    (net (code "60") (name "/RDAL2") (class "Default")
      (node (ref "IC19") (pin "6") (pinfunction "D3_6") (pintype "input"))
      (node (ref "IC20") (pin "28") (pinfunction "TBR3_28") (pintype "input"))
      (node (ref "IC3") (pin "12") (pinfunction "Y4_12") (pintype "tri_state"))
    )
    (net (code "61") (name "/RDAL3") (class "Default")
      (node (ref "IC20") (pin "29") (pinfunction "TBR4_29") (pintype "input"))
      (node (ref "IC3") (pin "14") (pinfunction "Y3_14") (pintype "tri_state"))
      (node (ref "IC5") (pin "14") (pinfunction "B5_14") (pintype "input"))
    )
    (net (code "62") (name "/RDAL4") (class "Default")
      (node (ref "IC20") (pin "30") (pinfunction "TBR5_30") (pintype "input"))
      (node (ref "IC3") (pin "16") (pinfunction "Y2_16") (pintype "tri_state"))
      (node (ref "IC5") (pin "22") (pinfunction "B9_22") (pintype "input"))
    )
    (net (code "63") (name "/RDAL5") (class "Default")
      (node (ref "IC20") (pin "31") (pinfunction "TBR6_31") (pintype "input"))
      (node (ref "IC3") (pin "18") (pinfunction "Y1_18") (pintype "tri_state"))
      (node (ref "IC5") (pin "16") (pinfunction "B6_16") (pintype "input"))
    )
    (net (code "64") (name "/RDAL6") (class "Default")
      (node (ref "IC13") (pin "12") (pinfunction "D_12") (pintype "input"))
      (node (ref "IC13") (pin "2") (pinfunction "D_2") (pintype "input"))
      (node (ref "IC20") (pin "32") (pinfunction "TBR7_32") (pintype "input"))
      (node (ref "IC3") (pin "5") (pinfunction "Y3_5") (pintype "tri_state"))
      (node (ref "IC5") (pin "18") (pinfunction "B7_18") (pintype "input"))
    )
    (net (code "65") (name "/RDAL7") (class "Default")
      (node (ref "IC20") (pin "33") (pinfunction "TBR8_33") (pintype "input"))
      (node (ref "IC3") (pin "3") (pinfunction "Y4_3") (pintype "tri_state"))
      (node (ref "IC5") (pin "20") (pinfunction "B8_20") (pintype "input"))
    )
    (net (code "66") (name "/RDAL8") (class "Default")
      (node (ref "IC1") (pin "9") (pinfunction "Y1_9") (pintype "tri_state"))
      (node (ref "IC5") (pin "10") (pinfunction "B4_10") (pintype "input"))
    )
    (net (code "67") (name "/RDAL9") (class "Default")
      (node (ref "IC1") (pin "12") (pinfunction "Y4_12") (pintype "tri_state"))
      (node (ref "IC5") (pin "8") (pinfunction "B3_8") (pintype "input"))
    )
    (net (code "68") (name "/RDAL10") (class "Default")
      (node (ref "IC1") (pin "14") (pinfunction "Y3_14") (pintype "tri_state"))
      (node (ref "IC5") (pin "6") (pinfunction "B2_6") (pintype "input"))
    )
    (net (code "69") (name "/RDAL11") (class "Default")
      (node (ref "IC1") (pin "16") (pinfunction "Y2_16") (pintype "tri_state"))
      (node (ref "IC5") (pin "4") (pinfunction "B1_4") (pintype "input"))
    )
    (net (code "70") (name "/RDAL12") (class "Default")
      (node (ref "IC1") (pin "18") (pinfunction "Y1_18") (pintype "tri_state"))
      (node (ref "IC5") (pin "2") (pinfunction "B0_2") (pintype "input"))
    )
    (net (code "71") (name "/RDATA0") (class "Default")
      (node (ref "IC20") (pin "20") (pinfunction "RRI_20") (pintype "input"))
      (node (ref "IC21") (pin "4") (pinfunction "O_4") (pintype "output"))
    )
    (net (code "72") (name "/RDCOK") (class "Default")
      (node (ref "IC1") (pin "7") (pinfunction "Y2_7") (pintype "tri_state"))
      (node (ref "IC20") (pin "21") (pinfunction "MR_21") (pintype "input"))
      (node (ref "IC27") (pin "5") (pinfunction "CP_5") (pintype "input"))
    )
    (net (code "73") (name "/RDIN") (class "Default")
      (node (ref "IC10") (pin "1") (pinfunction "I0_1") (pintype "input"))
      (node (ref "IC17") (pin "11") (pinfunction "CLK_11") (pintype "input"))
      (node (ref "IC17") (pin "3") (pinfunction "CLK_3") (pintype "input"))
      (node (ref "IC2") (pin "12") (pinfunction "Y4_12") (pintype "tri_state"))
    )
    (net (code "74") (name "/RDOUT") (class "Default")
      (node (ref "IC10") (pin "12") (pinfunction "I0_12") (pintype "input"))
      (node (ref "IC2") (pin "7") (pinfunction "Y2_7") (pintype "tri_state"))
    )
    (net (code "75") (name "/RDR+") (class "Default")
      (node (ref "D3") (pin "C") (pinfunction "C_C") (pintype "passive"))
      (node (ref "Q7") (pin "3") (pinfunction "C_3") (pintype "passive"))
      (node (ref "SV1") (pin "6") (pinfunction "6_6") (pintype "passive"))
    )
    (net (code "76") (name "/RDR-") (class "Default")
      (node (ref "R1") (pin "2") (pinfunction "2_2") (pintype "passive"))
      (node (ref "SV1") (pin "9") (pinfunction "9_9") (pintype "passive"))
    )
    (net (code "77") (name "/RIAKI") (class "Default")
      (node (ref "IC16") (pin "10") (pinfunction "I1_10") (pintype "input"))
      (node (ref "IC18") (pin "1") (pinfunction "I0_1") (pintype "input"))
      (node (ref "IC2") (pin "18") (pinfunction "Y1_18") (pintype "tri_state"))
      (node (ref "IC9") (pin "1") (pinfunction "I0_1") (pintype "input"))
    )
    (net (code "78") (name "/RIE") (class "Default")
      (node (ref "IC11") (pin "13") (pinfunction "I1_13") (pintype "input"))
      (node (ref "IC13") (pin "5") (pinfunction "Q_5") (pintype "output"))
      (node (ref "IC14") (pin "9") (pinfunction "I0_9") (pintype "input"))
      (node (ref "IC8") (pin "11") (pinfunction "3A_11") (pintype "input"))
    )
    (net (code "79") (name "/RINIT") (class "Default")
      (node (ref "IC2") (pin "5") (pinfunction "Y3_5") (pintype "tri_state"))
      (node (ref "IC2") (pin "6") (pinfunction "A3_6") (pintype "input"))
      (node (ref "IC21") (pin "3") (pinfunction "I1_3") (pintype "input"))
    )
    (net (code "80") (name "/RIRQ") (class "Default")
      (node (ref "IC17") (pin "6") (pinfunction "~{Q}_6") (pintype "output"))
      (node (ref "IC18") (pin "2") (pinfunction "I1_2") (pintype "input"))
    )
    (net (code "81") (name "/RRDY") (class "Default")
      (node (ref "IC14") (pin "10") (pinfunction "I1_10") (pintype "input"))
      (node (ref "IC15") (pin "5") (pinfunction "Q_5") (pintype "output"))
    )
    (net (code "82") (name "/RRDYI") (class "Default")
      (node (ref "IC11") (pin "11") (pinfunction "O_11") (pintype "output"))
      (node (ref "IC14") (pin "11") (pinfunction "I2_11") (pintype "input"))
      (node (ref "IC15") (pin "3") (pinfunction "CLK_3") (pintype "input"))
    )
    (net (code "83") (name "/RSYNC") (class "Default")
      (node (ref "IC2") (pin "16") (pinfunction "Y2_16") (pintype "tri_state"))
      (node (ref "IC2") (pin "17") (pinfunction "A4_17") (pintype "input"))
    )
    (net (code "84") (name "/RTS") (class "Default")
      (node (ref "IC24") (pin "11") (pinfunction "O_11") (pintype "output"))
      (node (ref "SV1") (pin "7") (pinfunction "7_7") (pintype "passive"))
      (node (ref "SV1") (pin "8") (pinfunction "8_8") (pintype "passive"))
    )
    (net (code "85") (name "/RX+") (class "Default")
      (node (ref "CL1") (pin "2") (pinfunction "2_2") (pintype "passive"))
      (node (ref "R22") (pin "2") (pinfunction "2_2") (pintype "passive"))
      (node (ref "SV2") (pin "2") (pinfunction "2_2") (pintype "passive"))
    )
    (net (code "86") (name "/RX-") (class "Default")
      (node (ref "D1") (pin "C") (pinfunction "C_C") (pintype "passive"))
      (node (ref "IC28") (pin "1") (pinfunction "A_1") (pintype "passive"))
      (node (ref "R5") (pin "2") (pinfunction "2_2") (pintype "passive"))
      (node (ref "SV1") (pin "20") (pinfunction "20_20") (pintype "passive"))
    )
    (net (code "87") (name "/RXCL") (class "Default")
      (node (ref "IC16") (pin "3") (pinfunction "O_3") (pintype "output"))
      (node (ref "SV2") (pin "1") (pinfunction "1_1") (pintype "passive"))
    )
    (net (code "88") (name "/RXD") (class "Default")
      (node (ref "IC21") (pin "12") (pinfunction "I1_12") (pintype "input"))
      (node (ref "IC8") (pin "2") (pinfunction "1A_2") (pintype "input"))
      (node (ref "SV2") (pin "3") (pinfunction "3_3") (pintype "passive"))
    )
    (net (code "89") (name "/RXEIA") (class "Default")
      (node (ref "IC23") (pin "3") (pinfunction "O_3") (pintype "output"))
      (node (ref "SV1") (pin "13") (pinfunction "13_13") (pintype "passive"))
    )
    (net (code "90") (name "/SBRK") (class "Default")
      (node (ref "IC22") (pin "9") (pinfunction "Q_9") (pintype "output"))
      (node (ref "IC8") (pin "6") (pinfunction "2B_6") (pintype "input"))
    )
    (net (code "91") (name "/TDAL0") (class "Default")
      (node (ref "IC4") (pin "11") (pinfunction "A1_11") (pintype "input"))
      (node (ref "IC7") (pin "9") (pinfunction "3Y_9") (pintype "tri_state"))
      (node (ref "IC8") (pin "7") (pinfunction "2Y_7") (pintype "tri_state"))
    )
    (net (code "92") (name "/TDAL1") (class "Default")
      (node (ref "IC4") (pin "13") (pinfunction "A2_13") (pintype "input"))
      (node (ref "IC7") (pin "12") (pinfunction "4Y_12") (pintype "tri_state"))
      (node (ref "R12") (pin "2") (pinfunction "2_2") (pintype "passive"))
    )
    (net (code "93") (name "/TDAL2") (class "Default")
      (node (ref "IC4") (pin "8") (pinfunction "A4_8") (pintype "input"))
      (node (ref "IC6") (pin "4") (pinfunction "1Y_4") (pintype "output"))
    )
    (net (code "94") (name "/TDAL3") (class "Default")
      (node (ref "IC4") (pin "6") (pinfunction "A3_6") (pintype "input"))
      (node (ref "IC6") (pin "7") (pinfunction "2Y_7") (pintype "output"))
    )
    (net (code "95") (name "/TDAL4") (class "Default")
      (node (ref "IC4") (pin "4") (pinfunction "A2_4") (pintype "input"))
      (node (ref "IC6") (pin "9") (pinfunction "3Y_9") (pintype "output"))
    )
    (net (code "96") (name "/TDAL5") (class "Default")
      (node (ref "IC4") (pin "2") (pinfunction "A1_2") (pintype "input"))
      (node (ref "IC6") (pin "12") (pinfunction "4Y_12") (pintype "output"))
    )
    (net (code "97") (name "/TDAL6") (class "Default")
      (node (ref "IC4") (pin "15") (pinfunction "A3_15") (pintype "input"))
      (node (ref "IC7") (pin "7") (pinfunction "2Y_7") (pintype "tri_state"))
      (node (ref "IC8") (pin "9") (pinfunction "3Y_9") (pintype "tri_state"))
    )
    (net (code "98") (name "/TDAL7") (class "Default")
      (node (ref "IC4") (pin "17") (pinfunction "A4_17") (pintype "input"))
      (node (ref "IC7") (pin "4") (pinfunction "1Y_4") (pintype "tri_state"))
      (node (ref "IC8") (pin "12") (pinfunction "4Y_12") (pintype "tri_state"))
    )
    (net (code "99") (name "/TDAL15") (class "Default")
      (node (ref "IC8") (pin "4") (pinfunction "1Y_4") (pintype "tri_state"))
      (node (ref "IC9") (pin "13") (pinfunction "I1_13") (pintype "input"))
    )
    (net (code "100") (name "/TSB") (class "Default")
      (node (ref "IC20") (pin "36") (pinfunction "SBS_36") (pintype "input"))
      (node (ref "TSB") (pin "2") (pinfunction "2_2") (pintype "passive"))
    )
    (net (code "101") (name "/TX+") (class "Default")
      (node (ref "CL4") (pin "2") (pinfunction "2_2") (pintype "passive"))
      (node (ref "R24") (pin "2") (pinfunction "2_2") (pintype "passive"))
      (node (ref "SV1") (pin "18") (pinfunction "18_18") (pintype "passive"))
    )
    (net (code "102") (name "/TX-") (class "Default")
      (node (ref "D2") (pin "C") (pinfunction "C_C") (pintype "passive"))
      (node (ref "IC29") (pin "5") (pinfunction "COL_5") (pintype "passive"))
      (node (ref "Q2") (pin "1") (pinfunction "E_1") (pintype "passive"))
      (node (ref "SV1") (pin "19") (pinfunction "19_19") (pintype "passive"))
    )
    (net (code "103") (name "/TXD") (class "Default")
      (node (ref "IC24") (pin "4") (pinfunction "I0_4") (pintype "input"))
      (node (ref "IC24") (pin "5") (pinfunction "I1_5") (pintype "input"))
      (node (ref "IC26") (pin "8") (pinfunction "O_8") (pintype "output"))
      (node (ref "IC29") (pin "2") (pinfunction "C_2") (pintype "passive"))
    )
    (net (code "104") (name "/XCSR") (class "Default")
      (node (ref "IC12") (pin "6") (pinfunction "O_6") (pintype "output"))
      (node (ref "IC13") (pin "11") (pinfunction "CLK_11") (pintype "input"))
      (node (ref "IC22") (pin "11") (pinfunction "CLK_11") (pintype "input"))
    )
    (net (code "105") (name "/XDATA0") (class "Default")
      (node (ref "IC20") (pin "25") (pinfunction "TRO_25") (pintype "output"))
      (node (ref "IC26") (pin "9") (pinfunction "I0_9") (pintype "input"))
    )
    (net (code "106") (name "/XIE") (class "Default")
      (node (ref "IC13") (pin "9") (pinfunction "Q_9") (pintype "output"))
      (node (ref "IC14") (pin "2") (pinfunction "I1_2") (pintype "input"))
      (node (ref "IC26") (pin "4") (pinfunction "I0_4") (pintype "input"))
      (node (ref "IC8") (pin "10") (pinfunction "3B_10") (pintype "input"))
    )
    (net (code "107") (name "/XIRQ") (class "Default")
      (node (ref "IC16") (pin "9") (pinfunction "I0_9") (pintype "input"))
      (node (ref "IC17") (pin "8") (pinfunction "~{Q}_8") (pintype "output"))
    )
    (net (code "108") (name "/XRDY") (class "Default")
      (node (ref "IC14") (pin "13") (pinfunction "I2_13") (pintype "input"))
      (node (ref "IC15") (pin "9") (pinfunction "Q_9") (pintype "output"))
    )
    (net (code "109") (name "/XRDY0") (class "Default")
      (node (ref "IC20") (pin "22") (pinfunction "TBRE_22") (pintype "tri_state"))
      (node (ref "IC26") (pin "5") (pinfunction "I1_5") (pintype "input"))
      (node (ref "IC8") (pin "13") (pinfunction "4B_13") (pintype "input"))
    )
    (net (code "110") (name "/XRDYI") (class "Default")
      (node (ref "IC14") (pin "1") (pinfunction "I0_1") (pintype "input"))
      (node (ref "IC15") (pin "11") (pinfunction "CLK_11") (pintype "input"))
      (node (ref "IC26") (pin "6") (pinfunction "O_6") (pintype "output"))
    )
    (net (code "111") (name "/~{A1R}") (class "Default")
      (node (ref "IC10") (pin "9") (pinfunction "I0_9") (pintype "input"))
      (node (ref "IC19") (pin "8") (pinfunction "~{Q4}_8") (pintype "output"))
      (node (ref "IC26") (pin "13") (pinfunction "I1_13") (pintype "input"))
    )
    (net (code "112") (name "/~{A2R}") (class "Default")
      (node (ref "IC12") (pin "4") (pinfunction "I1_4") (pintype "input"))
      (node (ref "IC18") (pin "4") (pinfunction "I1_4") (pintype "input"))
      (node (ref "IC19") (pin "11") (pinfunction "~{Q3}_11") (pintype "output"))
    )
    (net (code "113") (name "/~{BBS7}") (class "Default")
      (node (ref "EDGE$") (pin "AP2") (pinfunction "1_AP2") (pintype "bidirectional"))
      (node (ref "IC2") (pin "11") (pinfunction "A1_11") (pintype "input"))
    )
    (net (code "114") (name "/~{BDAL0}") (class "Default")
      (node (ref "EDGE$") (pin "AU2") (pinfunction "1_AU2") (pintype "bidirectional"))
      (node (ref "IC3") (pin "11") (pinfunction "A1_11") (pintype "input"))
      (node (ref "IC4") (pin "9") (pinfunction "Y1_9") (pintype "tri_state"))
    )
    (net (code "115") (name "/~{BDAL1}") (class "Default")
      (node (ref "EDGE$") (pin "AV2") (pinfunction "1_AV2") (pintype "bidirectional"))
      (node (ref "IC3") (pin "13") (pinfunction "A2_13") (pintype "input"))
      (node (ref "IC4") (pin "7") (pinfunction "Y2_7") (pintype "tri_state"))
    )
    (net (code "116") (name "/~{BDAL2}") (class "Default")
      (node (ref "EDGE$") (pin "BE2") (pinfunction "1_BE2") (pintype "bidirectional"))
      (node (ref "IC3") (pin "8") (pinfunction "A4_8") (pintype "input"))
      (node (ref "IC4") (pin "12") (pinfunction "Y4_12") (pintype "tri_state"))
    )
    (net (code "117") (name "/~{BDAL3}") (class "Default")
      (node (ref "EDGE$") (pin "BF2") (pinfunction "1_BF2") (pintype "bidirectional"))
      (node (ref "IC3") (pin "6") (pinfunction "A3_6") (pintype "input"))
      (node (ref "IC4") (pin "14") (pinfunction "Y3_14") (pintype "tri_state"))
    )
    (net (code "118") (name "/~{BDAL4}") (class "Default")
      (node (ref "EDGE$") (pin "BH2") (pinfunction "1_BH2") (pintype "bidirectional"))
      (node (ref "IC3") (pin "4") (pinfunction "A2_4") (pintype "input"))
      (node (ref "IC4") (pin "16") (pinfunction "Y2_16") (pintype "tri_state"))
    )
    (net (code "119") (name "/~{BDAL5}") (class "Default")
      (node (ref "EDGE$") (pin "BJ2") (pinfunction "1_BJ2") (pintype "bidirectional"))
      (node (ref "IC3") (pin "2") (pinfunction "A1_2") (pintype "input"))
      (node (ref "IC4") (pin "18") (pinfunction "Y1_18") (pintype "tri_state"))
    )
    (net (code "120") (name "/~{BDAL6}") (class "Default")
      (node (ref "EDGE$") (pin "BK2") (pinfunction "1_BK2") (pintype "bidirectional"))
      (node (ref "IC3") (pin "15") (pinfunction "A3_15") (pintype "input"))
      (node (ref "IC4") (pin "5") (pinfunction "Y3_5") (pintype "tri_state"))
    )
    (net (code "121") (name "/~{BDAL7}") (class "Default")
      (node (ref "EDGE$") (pin "BL2") (pinfunction "1_BL2") (pintype "bidirectional"))
      (node (ref "IC3") (pin "17") (pinfunction "A4_17") (pintype "input"))
      (node (ref "IC4") (pin "3") (pinfunction "Y4_3") (pintype "tri_state"))
    )
    (net (code "122") (name "/~{BDAL8}") (class "Default")
      (node (ref "EDGE$") (pin "BM2") (pinfunction "1_BM2") (pintype "bidirectional"))
      (node (ref "IC1") (pin "11") (pinfunction "A1_11") (pintype "input"))
    )
    (net (code "123") (name "/~{BDAL9}") (class "Default")
      (node (ref "EDGE$") (pin "BN2") (pinfunction "1_BN2") (pintype "bidirectional"))
      (node (ref "IC1") (pin "8") (pinfunction "A4_8") (pintype "input"))
    )
    (net (code "124") (name "/~{BDAL10}") (class "Default")
      (node (ref "EDGE$") (pin "BP2") (pinfunction "1_BP2") (pintype "bidirectional"))
      (node (ref "IC1") (pin "6") (pinfunction "A3_6") (pintype "input"))
    )
    (net (code "125") (name "/~{BDAL11}") (class "Default")
      (node (ref "EDGE$") (pin "BR2") (pinfunction "1_BR2") (pintype "bidirectional"))
      (node (ref "IC1") (pin "4") (pinfunction "A2_4") (pintype "input"))
    )
    (net (code "126") (name "/~{BDAL12}") (class "Default")
      (node (ref "EDGE$") (pin "BS2") (pinfunction "1_BS2") (pintype "bidirectional"))
      (node (ref "IC1") (pin "2") (pinfunction "A1_2") (pintype "input"))
    )
    (net (code "127") (name "/~{BDAL15}") (class "Default")
      (node (ref "EDGE$") (pin "BV2") (pinfunction "1_BV2") (pintype "bidirectional"))
      (node (ref "IC9") (pin "11") (pinfunction "O_11") (pintype "open_collector"))
    )
    (net (code "128") (name "/~{BDIN}") (class "Default")
      (node (ref "EDGE$") (pin "AH2") (pinfunction "1_AH2") (pintype "bidirectional"))
      (node (ref "IC2") (pin "8") (pinfunction "A4_8") (pintype "input"))
    )
    (net (code "129") (name "/~{BDOUT}") (class "Default")
      (node (ref "EDGE$") (pin "AE2") (pinfunction "1_AE2") (pintype "bidirectional"))
      (node (ref "IC2") (pin "13") (pinfunction "A2_13") (pintype "input"))
    )
    (net (code "130") (name "/~{BHALT}") (class "Default")
      (node (ref "EDGE$") (pin "AP1") (pinfunction "1_AP1") (pintype "bidirectional"))
      (node (ref "H1") (pin "1") (pinfunction "1_1") (pintype "passive"))
    )
    (net (code "131") (name "/~{BIAKI}") (class "Default")
      (node (ref "EDGE$") (pin "AM2") (pinfunction "1_AM2") (pintype "bidirectional"))
      (node (ref "IC2") (pin "2") (pinfunction "A1_2") (pintype "input"))
    )
    (net (code "132") (name "/~{BIAKO}") (class "Default")
      (node (ref "EDGE$") (pin "AN2") (pinfunction "1_AN2") (pintype "bidirectional"))
      (node (ref "IC9") (pin "3") (pinfunction "O_3") (pintype "open_collector"))
      (node (ref "R34") (pin "2") (pinfunction "2_2") (pintype "passive"))
      (node (ref "R35") (pin "2") (pinfunction "2_2") (pintype "passive"))
    )
    (net (code "133") (name "/~{BINIT}") (class "Default")
      (node (ref "EDGE$") (pin "AT2") (pinfunction "1_AT2") (pintype "bidirectional"))
      (node (ref "IC2") (pin "15") (pinfunction "A3_15") (pintype "input"))
    )
    (net (code "134") (name "/~{BIRQ4}") (class "Default")
      (node (ref "EDGE$") (pin "AL2") (pinfunction "1_AL2") (pintype "bidirectional"))
      (node (ref "IC9") (pin "8") (pinfunction "O_8") (pintype "open_collector"))
    )
    (net (code "135") (name "/~{BRPLY}") (class "Default")
      (node (ref "EDGE$") (pin "AF2") (pinfunction "1_AF2") (pintype "bidirectional"))
      (node (ref "IC9") (pin "6") (pinfunction "O_6") (pintype "open_collector"))
    )
    (net (code "136") (name "/~{BSYNC}") (class "Default")
      (node (ref "EDGE$") (pin "AJ2") (pinfunction "1_AJ2") (pintype "bidirectional"))
      (node (ref "IC2") (pin "4") (pinfunction "A2_4") (pintype "input"))
    )
    (net (code "137") (name "/~{BUF}") (class "Default")
      (node (ref "IC10") (pin "8") (pinfunction "O_8") (pintype "output"))
      (node (ref "IC21") (pin "8") (pinfunction "I0_8") (pintype "input"))
      (node (ref "IC8") (pin "15") (pinfunction "G_15") (pintype "input"))
    )
    (net (code "138") (name "/~{CTS}") (class "Default")
      (node (ref "IC21") (pin "5") (pinfunction "I0_5") (pintype "input"))
      (node (ref "IC23") (pin "11") (pinfunction "O_11") (pintype "output"))
    )
    (net (code "139") (name "/~{DIN}") (class "Default")
      (node (ref "IC21") (pin "9") (pinfunction "I1_9") (pintype "input"))
      (node (ref "IC26") (pin "3") (pinfunction "O_3") (pintype "output"))
      (node (ref "IC4") (pin "1") (pinfunction "G_1") (pintype "input"))
      (node (ref "IC4") (pin "19") (pinfunction "G_19") (pintype "input"))
    )
    (net (code "140") (name "/~{DSR}") (class "Default")
      (node (ref "IC21") (pin "6") (pinfunction "I1_6") (pintype "input"))
      (node (ref "IC23") (pin "8") (pinfunction "O_8") (pintype "output"))
    )
    (net (code "141") (name "/~{IIAKI}") (class "Default")
      (node (ref "IC11") (pin "4") (pinfunction "I0_4") (pintype "input"))
      (node (ref "IC15") (pin "13") (pinfunction "CLR_13") (pintype "input"))
      (node (ref "IC18") (pin "12") (pinfunction "O_12") (pintype "output"))
    )
    (net (code "142") (name "/~{INIT}") (class "Default")
      (node (ref "IC13") (pin "1") (pinfunction "CLR_1") (pintype "input"))
      (node (ref "IC13") (pin "13") (pinfunction "CLR_13") (pintype "input"))
      (node (ref "IC15") (pin "4") (pinfunction "PRE_4") (pintype "input"))
      (node (ref "IC17") (pin "10") (pinfunction "PRE_10") (pintype "input"))
      (node (ref "IC17") (pin "4") (pinfunction "PRE_4") (pintype "input"))
      (node (ref "IC2") (pin "14") (pinfunction "Y3_14") (pintype "tri_state"))
      (node (ref "IC22") (pin "13") (pinfunction "CLR_13") (pintype "input"))
    )
    (net (code "143") (name "/~{MYDIN}") (class "Default")
      (node (ref "IC10") (pin "3") (pinfunction "O_3") (pintype "output"))
      (node (ref "IC14") (pin "3") (pinfunction "I0_3") (pintype "input"))
      (node (ref "IC16") (pin "12") (pinfunction "I0_12") (pintype "input"))
      (node (ref "IC26") (pin "2") (pinfunction "I1_2") (pintype "input"))
    )
    (net (code "144") (name "/~{MYDOUT}") (class "Default")
      (node (ref "IC10") (pin "11") (pinfunction "O_11") (pintype "output"))
      (node (ref "IC12") (pin "13") (pinfunction "I2_13") (pintype "input"))
      (node (ref "IC12") (pin "5") (pinfunction "I2_5") (pintype "input"))
      (node (ref "IC12") (pin "9") (pinfunction "I0_9") (pintype "input"))
      (node (ref "IC14") (pin "5") (pinfunction "I2_5") (pintype "input"))
    )
    (net (code "145") (name "/~{MYIO}") (class "Default")
      (node (ref "IC10") (pin "6") (pinfunction "O_6") (pintype "output"))
      (node (ref "IC19") (pin "2") (pinfunction "D1_2") (pintype "input"))
    )
    (net (code "146") (name "/~{NOEOT}") (class "Default")
      (node (ref "IC21") (pin "13") (pinfunction "O_13") (pintype "output"))
      (node (ref "IC25") (pin "13") (pinfunction "~{MR}_13") (pintype "input"))
    )
    (net (code "147") (name "/~{RBUF}") (class "Default")
      (node (ref "IC18") (pin "6") (pinfunction "O_6") (pintype "output"))
      (node (ref "IC20") (pin "18") (pinfunction "~{DRR}_18") (pintype "input"))
    )
    (net (code "148") (name "/~{RIRQ}") (class "Default")
      (node (ref "IC11") (pin "1") (pinfunction "I0_1") (pintype "input"))
      (node (ref "IC17") (pin "5") (pinfunction "Q_5") (pintype "output"))
    )
    (net (code "149") (name "/~{RRUN}") (class "Default")
      (node (ref "IC21") (pin "11") (pinfunction "I0_11") (pintype "input"))
      (node (ref "IC22") (pin "6") (pinfunction "~{Q}_6") (pintype "output"))
      (node (ref "ZD4") (pin "A") (pinfunction "A_A") (pintype "passive"))
    )
    (net (code "150") (name "/~{RSTOP}") (class "Default")
      (node (ref "IC21") (pin "1") (pinfunction "O_1") (pintype "output"))
      (node (ref "IC22") (pin "1") (pinfunction "CLR_1") (pintype "input"))
    )
    (net (code "151") (name "/~{RXEIA}") (class "Default")
      (node (ref "IC23") (pin "1") (pinfunction "I_1") (pintype "input"))
      (node (ref "SV1") (pin "12") (pinfunction "12_12") (pintype "passive"))
    )
    (net (code "152") (name "/~{SBRK}") (class "Default")
      (node (ref "IC22") (pin "8") (pinfunction "~{Q}_8") (pintype "output"))
      (node (ref "IC26") (pin "10") (pinfunction "I1_10") (pintype "input"))
    )
    (net (code "153") (name "/~{SYNC}") (class "Default")
      (node (ref "IC19") (pin "13") (pinfunction "C12_13") (pintype "input"))
      (node (ref "IC19") (pin "4") (pinfunction "C34_4") (pintype "input"))
      (node (ref "IC2") (pin "3") (pinfunction "Y4_3") (pintype "tri_state"))
    )
    (net (code "154") (name "/~{TXEIA}") (class "Default")
      (node (ref "C1") (pin "1") (pinfunction "1_1") (pintype "passive"))
      (node (ref "IC24") (pin "6") (pinfunction "O_6") (pintype "output"))
      (node (ref "SV1") (pin "11") (pinfunction "11_11") (pintype "passive"))
    )
    (net (code "155") (name "/~{XBUF}") (class "Default")
      (node (ref "IC18") (pin "8") (pinfunction "O_8") (pintype "output"))
      (node (ref "IC20") (pin "23") (pinfunction "~{TBRL}_23") (pintype "input"))
    )
    (net (code "156") (name "/~{XIAKI}") (class "Default")
      (node (ref "IC11") (pin "5") (pinfunction "I1_5") (pintype "input"))
      (node (ref "IC15") (pin "1") (pinfunction "CLR_1") (pintype "input"))
      (node (ref "IC16") (pin "8") (pinfunction "O_8") (pintype "output"))
    )
    (net (code "157") (name "/~{XIRQ}") (class "Default")
      (node (ref "IC11") (pin "2") (pinfunction "I1_2") (pintype "input"))
      (node (ref "IC17") (pin "9") (pinfunction "Q_9") (pintype "output"))
      (node (ref "IC18") (pin "13") (pinfunction "I2_13") (pintype "input"))
      (node (ref "IC6") (pin "2") (pinfunction "1A_2") (pintype "input"))
    )
    (net (code "158") (name "GND") (class "Default")
      (node (ref "A10") (pin "1") (pinfunction "1_1") (pintype "passive"))
      (node (ref "A11") (pin "1") (pinfunction "1_1") (pintype "passive"))
      (node (ref "A12") (pin "1") (pinfunction "1_1") (pintype "passive"))
      (node (ref "A3") (pin "1") (pinfunction "1_1") (pintype "passive"))
      (node (ref "A4") (pin "1") (pinfunction "1_1") (pintype "passive"))
      (node (ref "A5") (pin "1") (pinfunction "1_1") (pintype "passive"))
      (node (ref "A6") (pin "1") (pinfunction "1_1") (pintype "passive"))
      (node (ref "A7") (pin "1") (pinfunction "1_1") (pintype "passive"))
      (node (ref "A8") (pin "1") (pinfunction "1_1") (pintype "passive"))
      (node (ref "A9") (pin "1") (pinfunction "1_1") (pintype "passive"))
      (node (ref "C1") (pin "2") (pinfunction "2_2") (pintype "passive"))
      (node (ref "C10") (pin "-") (pinfunction "-_-") (pintype "passive"))
      (node (ref "C11") (pin "-") (pinfunction "-_-") (pintype "passive"))
      (node (ref "C12") (pin "2") (pinfunction "2_2") (pintype "passive"))
      (node (ref "C13") (pin "-") (pinfunction "-_-") (pintype "passive"))
      (node (ref "C14") (pin "2") (pinfunction "2_2") (pintype "passive"))
      (node (ref "C15") (pin "-") (pinfunction "-_-") (pintype "passive"))
      (node (ref "C16") (pin "-") (pinfunction "-_-") (pintype "passive"))
      (node (ref "C17") (pin "-") (pinfunction "-_-") (pintype "passive"))
      (node (ref "C18") (pin "-") (pinfunction "-_-") (pintype "passive"))
      (node (ref "C19") (pin "2") (pinfunction "2_2") (pintype "passive"))
      (node (ref "C2") (pin "2") (pinfunction "2_2") (pintype "passive"))
      (node (ref "C20") (pin "-") (pinfunction "-_-") (pintype "passive"))
      (node (ref "C3") (pin "2") (pinfunction "2_2") (pintype "passive"))
      (node (ref "C4") (pin "2") (pinfunction "2_2") (pintype "passive"))
      (node (ref "C5") (pin "2") (pinfunction "2_2") (pintype "passive"))
      (node (ref "C6") (pin "2") (pinfunction "2_2") (pintype "passive"))
      (node (ref "C8") (pin "+") (pinfunction "+_+") (pintype "passive"))
      (node (ref "C9") (pin "-") (pinfunction "-_-") (pintype "passive"))
      (node (ref "D6") (pin "C") (pinfunction "C_C") (pintype "passive"))
      (node (ref "EDGE$") (pin "AJ1") (pinfunction "1_AJ1") (pintype "bidirectional"))
      (node (ref "EDGE$") (pin "AM1") (pinfunction "1_AM1") (pintype "bidirectional"))
      (node (ref "EDGE$") (pin "BC2") (pinfunction "1_BC2") (pintype "bidirectional"))
      (node (ref "EDGE$") (pin "BM1") (pinfunction "1_BM1") (pintype "bidirectional"))
      (node (ref "EDGE$") (pin "BT1") (pinfunction "1_BT1") (pintype "bidirectional"))
      (node (ref "EPS") (pin "1") (pinfunction "1_1") (pintype "passive"))
      (node (ref "FR0") (pin "2") (pinfunction "2_2") (pintype "passive"))
      (node (ref "FR1") (pin "2") (pinfunction "2_2") (pintype "passive"))
      (node (ref "FR2") (pin "2") (pinfunction "2_2") (pintype "passive"))
      (node (ref "FR3") (pin "2") (pinfunction "2_2") (pintype "passive"))
      (node (ref "IC1") (pin "1") (pinfunction "G_1") (pintype "input"))
      (node (ref "IC1") (pin "19") (pinfunction "G_19") (pintype "input"))
      (node (ref "IC12") (pin "1") (pinfunction "I0_1") (pintype "input"))
      (node (ref "IC12") (pin "2") (pinfunction "I1_2") (pintype "input"))
      (node (ref "IC2") (pin "1") (pinfunction "G_1") (pintype "input"))
      (node (ref "IC2") (pin "19") (pinfunction "G_19") (pintype "input"))
      (node (ref "IC20") (pin "16") (pinfunction "SFD_16") (pintype "input"))
      (node (ref "IC20") (pin "4") (pinfunction "RRD_4") (pintype "input"))
      (node (ref "IC24") (pin "12") (pinfunction "I0_12") (pintype "input"))
      (node (ref "IC24") (pin "13") (pinfunction "I1_13") (pintype "input"))
      (node (ref "IC24") (pin "7") (pinfunction "GND_7") (pintype "power_in"))
      (node (ref "IC25") (pin "10") (pinfunction "I1_10") (pintype "input"))
      (node (ref "IC25") (pin "11") (pinfunction "I3_11") (pintype "input"))
      (node (ref "IC25") (pin "3") (pinfunction "I2_3") (pintype "input"))
      (node (ref "IC25") (pin "4") (pinfunction "I0_4") (pintype "input"))
      (node (ref "IC28") (pin "4") (pinfunction "EMI_4") (pintype "passive"))
      (node (ref "IC3") (pin "1") (pinfunction "G_1") (pintype "input"))
      (node (ref "IC3") (pin "19") (pinfunction "G_19") (pintype "input"))
      (node (ref "IC5") (pin "11") (pinfunction "~{STB}_11") (pintype "input"))
      (node (ref "IC7") (pin "11") (pinfunction "3A_11") (pintype "input"))
      (node (ref "IC7") (pin "14") (pinfunction "4A_14") (pintype "input"))
      (node (ref "IC8") (pin "3") (pinfunction "1B_3") (pintype "input"))
      (node (ref "IC8") (pin "5") (pinfunction "2A_5") (pintype "input"))
      (node (ref "NB1") (pin "1") (pinfunction "1_1") (pintype "passive"))
      (node (ref "NB2") (pin "1") (pinfunction "1_1") (pintype "passive"))
      (node (ref "NP") (pin "1") (pinfunction "1_1") (pintype "passive"))
      (node (ref "Q1") (pin "1") (pinfunction "E_1") (pintype "passive"))
      (node (ref "Q4") (pin "1") (pinfunction "E_1") (pintype "passive"))
      (node (ref "Q6") (pin "3") (pinfunction "C_3") (pintype "passive"))
      (node (ref "R12") (pin "1") (pinfunction "1_1") (pintype "passive"))
      (node (ref "R35") (pin "1") (pinfunction "1_1") (pintype "passive"))
      (node (ref "SV1") (pin "1") (pinfunction "1_1") (pintype "passive"))
      (node (ref "SV1") (pin "16") (pinfunction "16_16") (pintype "passive"))
      (node (ref "SV2") (pin "4") (pinfunction "4_4") (pintype "passive"))
      (node (ref "SV2") (pin "5") (pinfunction "5_5") (pintype "passive"))
      (node (ref "TSB") (pin "1") (pinfunction "1_1") (pintype "passive"))
      (node (ref "V3") (pin "1") (pinfunction "1_1") (pintype "passive"))
      (node (ref "V4") (pin "1") (pinfunction "1_1") (pintype "passive"))
      (node (ref "V5") (pin "1") (pinfunction "1_1") (pintype "passive"))
      (node (ref "V6") (pin "1") (pinfunction "1_1") (pintype "passive"))
      (node (ref "V7") (pin "1") (pinfunction "1_1") (pintype "passive"))
    )
    (net (code "159") (name "Net-(C7-Pad-)") (class "Default")
      (node (ref "C7") (pin "-") (pinfunction "-_-") (pintype "passive"))
      (node (ref "D5") (pin "C") (pinfunction "C_C") (pintype "passive"))
      (node (ref "D6") (pin "A") (pinfunction "A_A") (pintype "passive"))
    )
    (net (code "160") (name "Net-(D3-PadA)") (class "Default")
      (node (ref "D3") (pin "A") (pinfunction "A_A") (pintype "passive"))
      (node (ref "R1") (pin "1") (pinfunction "1_1") (pintype "passive"))
      (node (ref "R2") (pin "1") (pinfunction "1_1") (pintype "passive"))
    )
    (net (code "161") (name "Net-(IC6A-2A)") (class "Default")
      (node (ref "IC6") (pin "5") (pinfunction "2A_5") (pintype "input"))
      (node (ref "R16") (pin "2") (pinfunction "2_2") (pintype "passive"))
      (node (ref "V3") (pin "2") (pinfunction "2_2") (pintype "passive"))
    )
    (net (code "162") (name "Net-(IC6A-3A)") (class "Default")
      (node (ref "IC6") (pin "11") (pinfunction "3A_11") (pintype "input"))
      (node (ref "R17") (pin "2") (pinfunction "2_2") (pintype "passive"))
      (node (ref "V4") (pin "2") (pinfunction "2_2") (pintype "passive"))
    )
    (net (code "163") (name "Net-(IC6A-4A)") (class "Default")
      (node (ref "IC6") (pin "14") (pinfunction "4A_14") (pintype "input"))
      (node (ref "R18") (pin "2") (pinfunction "2_2") (pintype "passive"))
      (node (ref "V5") (pin "2") (pinfunction "2_2") (pintype "passive"))
    )
    (net (code "164") (name "Net-(IC7A-1A)") (class "Default")
      (node (ref "IC7") (pin "2") (pinfunction "1A_2") (pintype "input"))
      (node (ref "R15") (pin "2") (pinfunction "2_2") (pintype "passive"))
      (node (ref "V7") (pin "2") (pinfunction "2_2") (pintype "passive"))
    )
    (net (code "165") (name "Net-(IC7A-2A)") (class "Default")
      (node (ref "IC7") (pin "5") (pinfunction "2A_5") (pintype "input"))
      (node (ref "R14") (pin "2") (pinfunction "2_2") (pintype "passive"))
      (node (ref "V6") (pin "2") (pinfunction "2_2") (pintype "passive"))
    )
    (net (code "166") (name "Net-(IC23A-RC)") (class "Default")
      (node (ref "C2") (pin "1") (pinfunction "1_1") (pintype "passive"))
      (node (ref "IC23") (pin "2") (pinfunction "RC_2") (pintype "input"))
    )
    (net (code "167") (name "Net-(IC23C-RC)") (class "Default")
      (node (ref "C4") (pin "1") (pinfunction "1_1") (pintype "passive"))
      (node (ref "IC23") (pin "9") (pinfunction "RC_9") (pintype "input"))
    )
    (net (code "168") (name "Net-(IC23D-RC)") (class "Default")
      (node (ref "C3") (pin "1") (pinfunction "1_1") (pintype "passive"))
      (node (ref "IC23") (pin "12") (pinfunction "RC_12") (pintype "input"))
    )
    (net (code "169") (name "Net-(IC25A-Q0)") (class "Default")
      (node (ref "IC25") (pin "5") (pinfunction "Q0_5") (pintype "output"))
      (node (ref "IC25") (pin "6") (pinfunction "/5_6") (pintype "bidirectional"))
    )
    (net (code "170") (name "Net-(IC27A-IX)") (class "Default")
      (node (ref "C5") (pin "1") (pinfunction "1_1") (pintype "passive"))
      (node (ref "IC27") (pin "7") (pinfunction "IX_7") (pintype "input"))
      (node (ref "K1") (pin "1") (pinfunction "1_1") (pintype "passive"))
      (node (ref "R9") (pin "1") (pinfunction "1_1") (pintype "passive"))
    )
    (net (code "171") (name "Net-(IC27A-OX)") (class "Default")
      (node (ref "C6") (pin "1") (pinfunction "1_1") (pintype "passive"))
      (node (ref "IC27") (pin "6") (pinfunction "OX_6") (pintype "output"))
      (node (ref "K1") (pin "2") (pinfunction "2_2") (pintype "passive"))
      (node (ref "R9") (pin "2") (pinfunction "2_2") (pintype "passive"))
    )
    (net (code "172") (name "Net-(IC27A-S0)") (class "Default")
      (node (ref "FR0") (pin "1") (pinfunction "1_1") (pintype "passive"))
      (node (ref "IC27") (pin "14") (pinfunction "S0_14") (pintype "input"))
    )
    (net (code "173") (name "Net-(IC27A-S1)") (class "Default")
      (node (ref "FR1") (pin "1") (pinfunction "1_1") (pintype "passive"))
      (node (ref "IC27") (pin "13") (pinfunction "S1_13") (pintype "input"))
    )
    (net (code "174") (name "Net-(IC27A-S2)") (class "Default")
      (node (ref "FR2") (pin "1") (pinfunction "1_1") (pintype "passive"))
      (node (ref "IC27") (pin "12") (pinfunction "S2_12") (pintype "input"))
    )
    (net (code "175") (name "Net-(IC27A-S3)") (class "Default")
      (node (ref "FR3") (pin "1") (pinfunction "1_1") (pintype "passive"))
      (node (ref "IC27") (pin "11") (pinfunction "S3_11") (pintype "input"))
    )
    (net (code "176") (name "Net-(IC29-A)") (class "Default")
      (node (ref "IC29") (pin "1") (pinfunction "A_1") (pintype "passive"))
      (node (ref "R8") (pin "2") (pinfunction "2_2") (pintype "passive"))
    )
    (net (code "177") (name "Net-(IC29-BAS)") (class "Default")
      (node (ref "IC29") (pin "6") (pinfunction "BAS_6") (pintype "passive"))
      (node (ref "R7") (pin "2") (pinfunction "2_2") (pintype "passive"))
    )
    (net (code "178") (name "Net-(Q1-C)") (class "Default")
      (node (ref "H1") (pin "2") (pinfunction "2_2") (pintype "passive"))
      (node (ref "Q1") (pin "3") (pinfunction "C_3") (pintype "passive"))
    )
    (net (code "179") (name "Net-(Q4-C)") (class "Default")
      (node (ref "Q4") (pin "3") (pinfunction "C_3") (pintype "passive"))
      (node (ref "Q5") (pin "2") (pinfunction "B_2") (pintype "passive"))
      (node (ref "Q6") (pin "2") (pinfunction "B_2") (pintype "passive"))
      (node (ref "R11") (pin "2") (pinfunction "2_2") (pintype "passive"))
    )
    (net (code "180") (name "Net-(Q5-E)") (class "Default")
      (node (ref "C7") (pin "+") (pinfunction "+_+") (pintype "passive"))
      (node (ref "Q5") (pin "1") (pinfunction "E_1") (pintype "passive"))
      (node (ref "Q6") (pin "1") (pinfunction "E_1") (pintype "passive"))
    )
    (net (code "181") (name "Net-(Q7-B)") (class "Default")
      (node (ref "Q7") (pin "2") (pinfunction "B_2") (pintype "passive"))
      (node (ref "R4") (pin "1") (pinfunction "1_1") (pintype "passive"))
      (node (ref "ZD4") (pin "C") (pinfunction "C_C") (pintype "passive"))
    )
    (net (code "182") (name "Net-(Q7-E)") (class "Default")
      (node (ref "Q7") (pin "1") (pinfunction "E_1") (pintype "passive"))
      (node (ref "R3") (pin "1") (pinfunction "1_1") (pintype "passive"))
    )
    (net (code "183") (name "VCC") (class "Default")
      (node (ref "C10") (pin "+") (pinfunction "+_+") (pintype "passive"))
      (node (ref "C11") (pin "+") (pinfunction "+_+") (pintype "passive"))
      (node (ref "C13") (pin "+") (pinfunction "+_+") (pintype "passive"))
      (node (ref "C14") (pin "1") (pinfunction "1_1") (pintype "passive"))
      (node (ref "C15") (pin "+") (pinfunction "+_+") (pintype "passive"))
      (node (ref "C20") (pin "+") (pinfunction "+_+") (pintype "passive"))
      (node (ref "C9") (pin "+") (pinfunction "+_+") (pintype "passive"))
      (node (ref "EDGE$") (pin "AA2") (pinfunction "1_AA2") (pintype "bidirectional"))
      (node (ref "EDGE$") (pin "BV1") (pinfunction "1_BV1") (pintype "bidirectional"))
      (node (ref "IC1") (pin "15") (pinfunction "A3_15") (pintype "input"))
      (node (ref "IC1") (pin "17") (pinfunction "A4_17") (pintype "input"))
      (node (ref "IC13") (pin "10") (pinfunction "PRE_10") (pintype "input"))
      (node (ref "IC13") (pin "4") (pinfunction "PRE_4") (pintype "input"))
      (node (ref "IC15") (pin "10") (pinfunction "PRE_10") (pintype "input"))
      (node (ref "IC15") (pin "12") (pinfunction "D_12") (pintype "input"))
      (node (ref "IC15") (pin "2") (pinfunction "D_2") (pintype "input"))
      (node (ref "IC16") (pin "13") (pinfunction "I1_13") (pintype "input"))
      (node (ref "IC16") (pin "2") (pinfunction "I1_2") (pintype "input"))
      (node (ref "IC17") (pin "1") (pinfunction "CLR_1") (pintype "input"))
      (node (ref "IC17") (pin "13") (pinfunction "CLR_13") (pintype "input"))
      (node (ref "IC19") (pin "3") (pinfunction "D2_3") (pintype "input"))
      (node (ref "IC20") (pin "34") (pinfunction "CRL_34") (pintype "input"))
      (node (ref "IC22") (pin "10") (pinfunction "PRE_10") (pintype "input"))
      (node (ref "IC22") (pin "4") (pinfunction "PRE_4") (pintype "input"))
      (node (ref "IC24") (pin "10") (pinfunction "I1_10") (pintype "input"))
      (node (ref "IC24") (pin "9") (pinfunction "I0_9") (pintype "input"))
      (node (ref "IC25") (pin "1") (pinfunction "~{LD}_1") (pintype "input"))
      (node (ref "IC27") (pin "15") (pinfunction "IM_15") (pintype "input"))
      (node (ref "IC27") (pin "4") (pinfunction "~{ECP}_4") (pintype "input"))
      (node (ref "R14") (pin "1") (pinfunction "1_1") (pintype "passive"))
      (node (ref "R15") (pin "1") (pinfunction "1_1") (pintype "passive"))
      (node (ref "R16") (pin "1") (pinfunction "1_1") (pintype "passive"))
      (node (ref "R17") (pin "1") (pinfunction "1_1") (pintype "passive"))
      (node (ref "R18") (pin "1") (pinfunction "1_1") (pintype "passive"))
      (node (ref "R19") (pin "1") (pinfunction "1_1") (pintype "passive"))
      (node (ref "R21") (pin "1") (pinfunction "1_1") (pintype "passive"))
      (node (ref "R23") (pin "1") (pinfunction "1_1") (pintype "passive"))
      (node (ref "R25") (pin "1") (pinfunction "1_1") (pintype "passive"))
      (node (ref "R26") (pin "1") (pinfunction "1_1") (pintype "passive"))
      (node (ref "R27") (pin "1") (pinfunction "1_1") (pintype "passive"))
      (node (ref "R28") (pin "1") (pinfunction "1_1") (pintype "passive"))
      (node (ref "R29") (pin "1") (pinfunction "1_1") (pintype "passive"))
      (node (ref "R31") (pin "1") (pinfunction "1_1") (pintype "passive"))
      (node (ref "R32") (pin "1") (pinfunction "1_1") (pintype "passive"))
      (node (ref "R34") (pin "1") (pinfunction "1_1") (pintype "passive"))
      (node (ref "R41") (pin "2") (pinfunction "2_2") (pintype "passive"))
      (node (ref "R6") (pin "1") (pinfunction "1_1") (pintype "passive"))
      (node (ref "R8") (pin "1") (pinfunction "1_1") (pintype "passive"))
    )
    (net (code "184") (name "unconnected-(IC1B-Y3-Pad5)") (class "Default")
      (node (ref "IC1") (pin "5") (pinfunction "Y3_5") (pintype "tri_state"))
    )
    (net (code "185") (name "unconnected-(IC1B-Y4-Pad3)") (class "Default")
      (node (ref "IC1") (pin "3") (pinfunction "Y4_3") (pintype "tri_state"))
    )
    (net (code "186") (name "unconnected-(IC13A-~{Q}-Pad6)") (class "Default")
      (node (ref "IC13") (pin "6") (pinfunction "~{Q}_6") (pintype "output"))
    )
    (net (code "187") (name "unconnected-(IC13B-~{Q}-Pad8)") (class "Default")
      (node (ref "IC13") (pin "8") (pinfunction "~{Q}_8") (pintype "output"))
    )
    (net (code "188") (name "unconnected-(IC15A-~{Q}-Pad6)") (class "Default")
      (node (ref "IC15") (pin "6") (pinfunction "~{Q}_6") (pintype "output"))
    )
    (net (code "189") (name "unconnected-(IC15B-~{Q}-Pad8)") (class "Default")
      (node (ref "IC15") (pin "8") (pinfunction "~{Q}_8") (pintype "output"))
    )
    (net (code "190") (name "unconnected-(IC19A-Q1-Pad16)") (class "Default")
      (node (ref "IC19") (pin "16") (pinfunction "Q1_16") (pintype "output"))
    )
    (net (code "191") (name "unconnected-(IC19A-Q2-Pad15)") (class "Default")
      (node (ref "IC19") (pin "15") (pinfunction "Q2_15") (pintype "output"))
    )
    (net (code "192") (name "unconnected-(IC19A-~{Q2}-Pad14)") (class "Default")
      (node (ref "IC19") (pin "14") (pinfunction "~{Q2}_14") (pintype "output"))
    )
    (net (code "193") (name "unconnected-(IC20A-OE-Pad15)") (class "Default")
      (node (ref "IC20") (pin "15") (pinfunction "OE_15") (pintype "tri_state"))
    )
    (net (code "194") (name "unconnected-(IC20A-PE-Pad13)") (class "Default")
      (node (ref "IC20") (pin "13") (pinfunction "PE_13") (pintype "tri_state"))
    )
    (net (code "195") (name "unconnected-(IC20A-TRE-Pad24)") (class "Default")
      (node (ref "IC20") (pin "24") (pinfunction "TRE_24") (pintype "output"))
    )
    (net (code "196") (name "unconnected-(IC22A-Q-Pad5)") (class "Default")
      (node (ref "IC22") (pin "5") (pinfunction "Q_5") (pintype "output"))
    )
    (net (code "197") (name "unconnected-(IC25A-Q1-Pad9)") (class "Default")
      (node (ref "IC25") (pin "9") (pinfunction "Q1_9") (pintype "output"))
    )
    (net (code "198") (name "unconnected-(IC25A-Q2-Pad2)") (class "Default")
      (node (ref "IC25") (pin "2") (pinfunction "Q2_2") (pintype "output"))
    )
    (net (code "199") (name "unconnected-(IC27A-CO-Pad9)") (class "Default")
      (node (ref "IC27") (pin "9") (pinfunction "CO_9") (pintype "output"))
    )
    (net (code "200") (name "unconnected-(IC27A-Q0-Pad1)") (class "Default")
      (node (ref "IC27") (pin "1") (pinfunction "Q0_1") (pintype "output"))
    )
    (net (code "201") (name "unconnected-(IC27A-Q2-Pad3)") (class "Default")
      (node (ref "IC27") (pin "3") (pinfunction "Q2_3") (pintype "output"))
    )
    (net (code "202") (name "unconnected-(IC28-BAS-Pad6)") (class "Default")
      (node (ref "IC28") (pin "6") (pinfunction "BAS_6") (pintype "passive"))
    )
    (net (code "203") (name "unconnected-(SV1-Pad2)") (class "Default")
      (node (ref "SV1") (pin "2") (pinfunction "2_2") (pintype "passive"))
    )
    (net (code "204") (name "unconnected-(SV1-Pad3)") (class "Default")
      (node (ref "SV1") (pin "3") (pinfunction "3_3") (pintype "passive"))
    )
    (net (code "205") (name "unconnected-(SV1-Pad4)") (class "Default")
      (node (ref "SV1") (pin "4") (pinfunction "4_4") (pintype "passive"))
    )
    (net (code "206") (name "unconnected-(SV1-Pad5)") (class "Default")
      (node (ref "SV1") (pin "5") (pinfunction "5_5") (pintype "passive"))
    )
  )
)
